# ASIC_1.net
KiCad netlist of a schematic drawn in Altium Designer
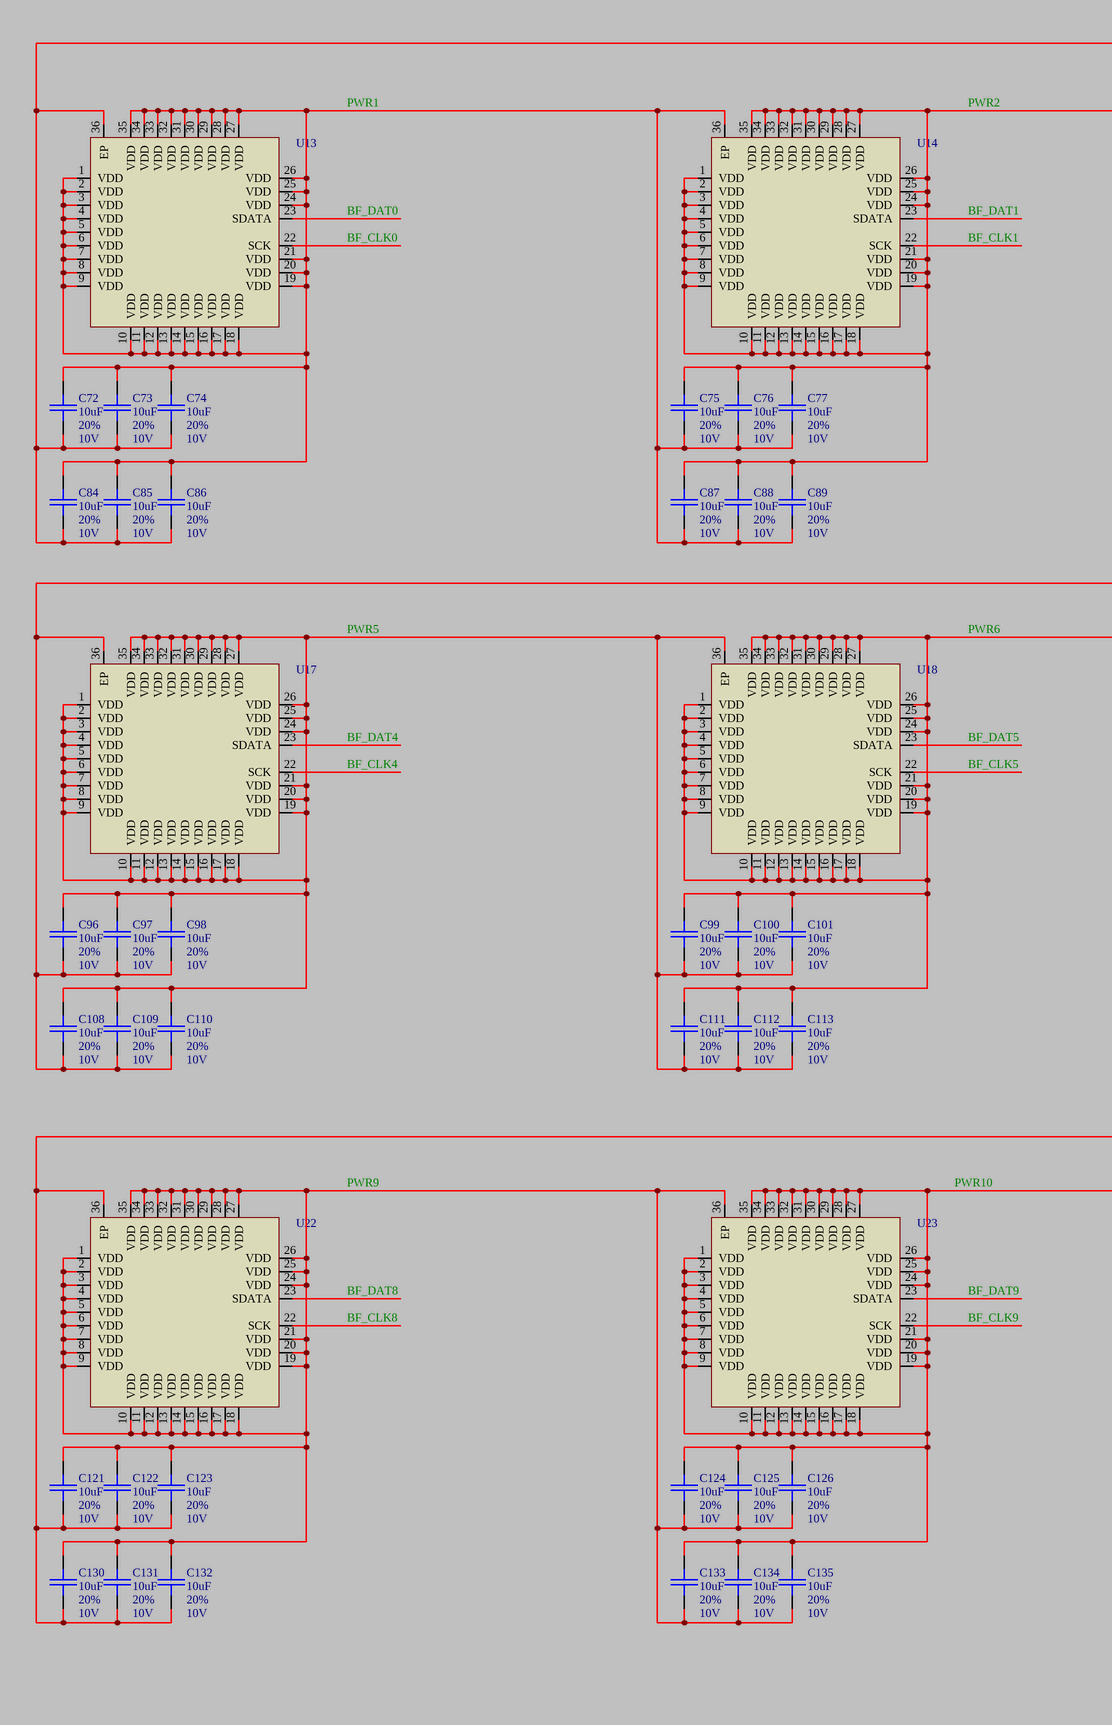
[diagram p0: ASIC_1.SchDoc, left]
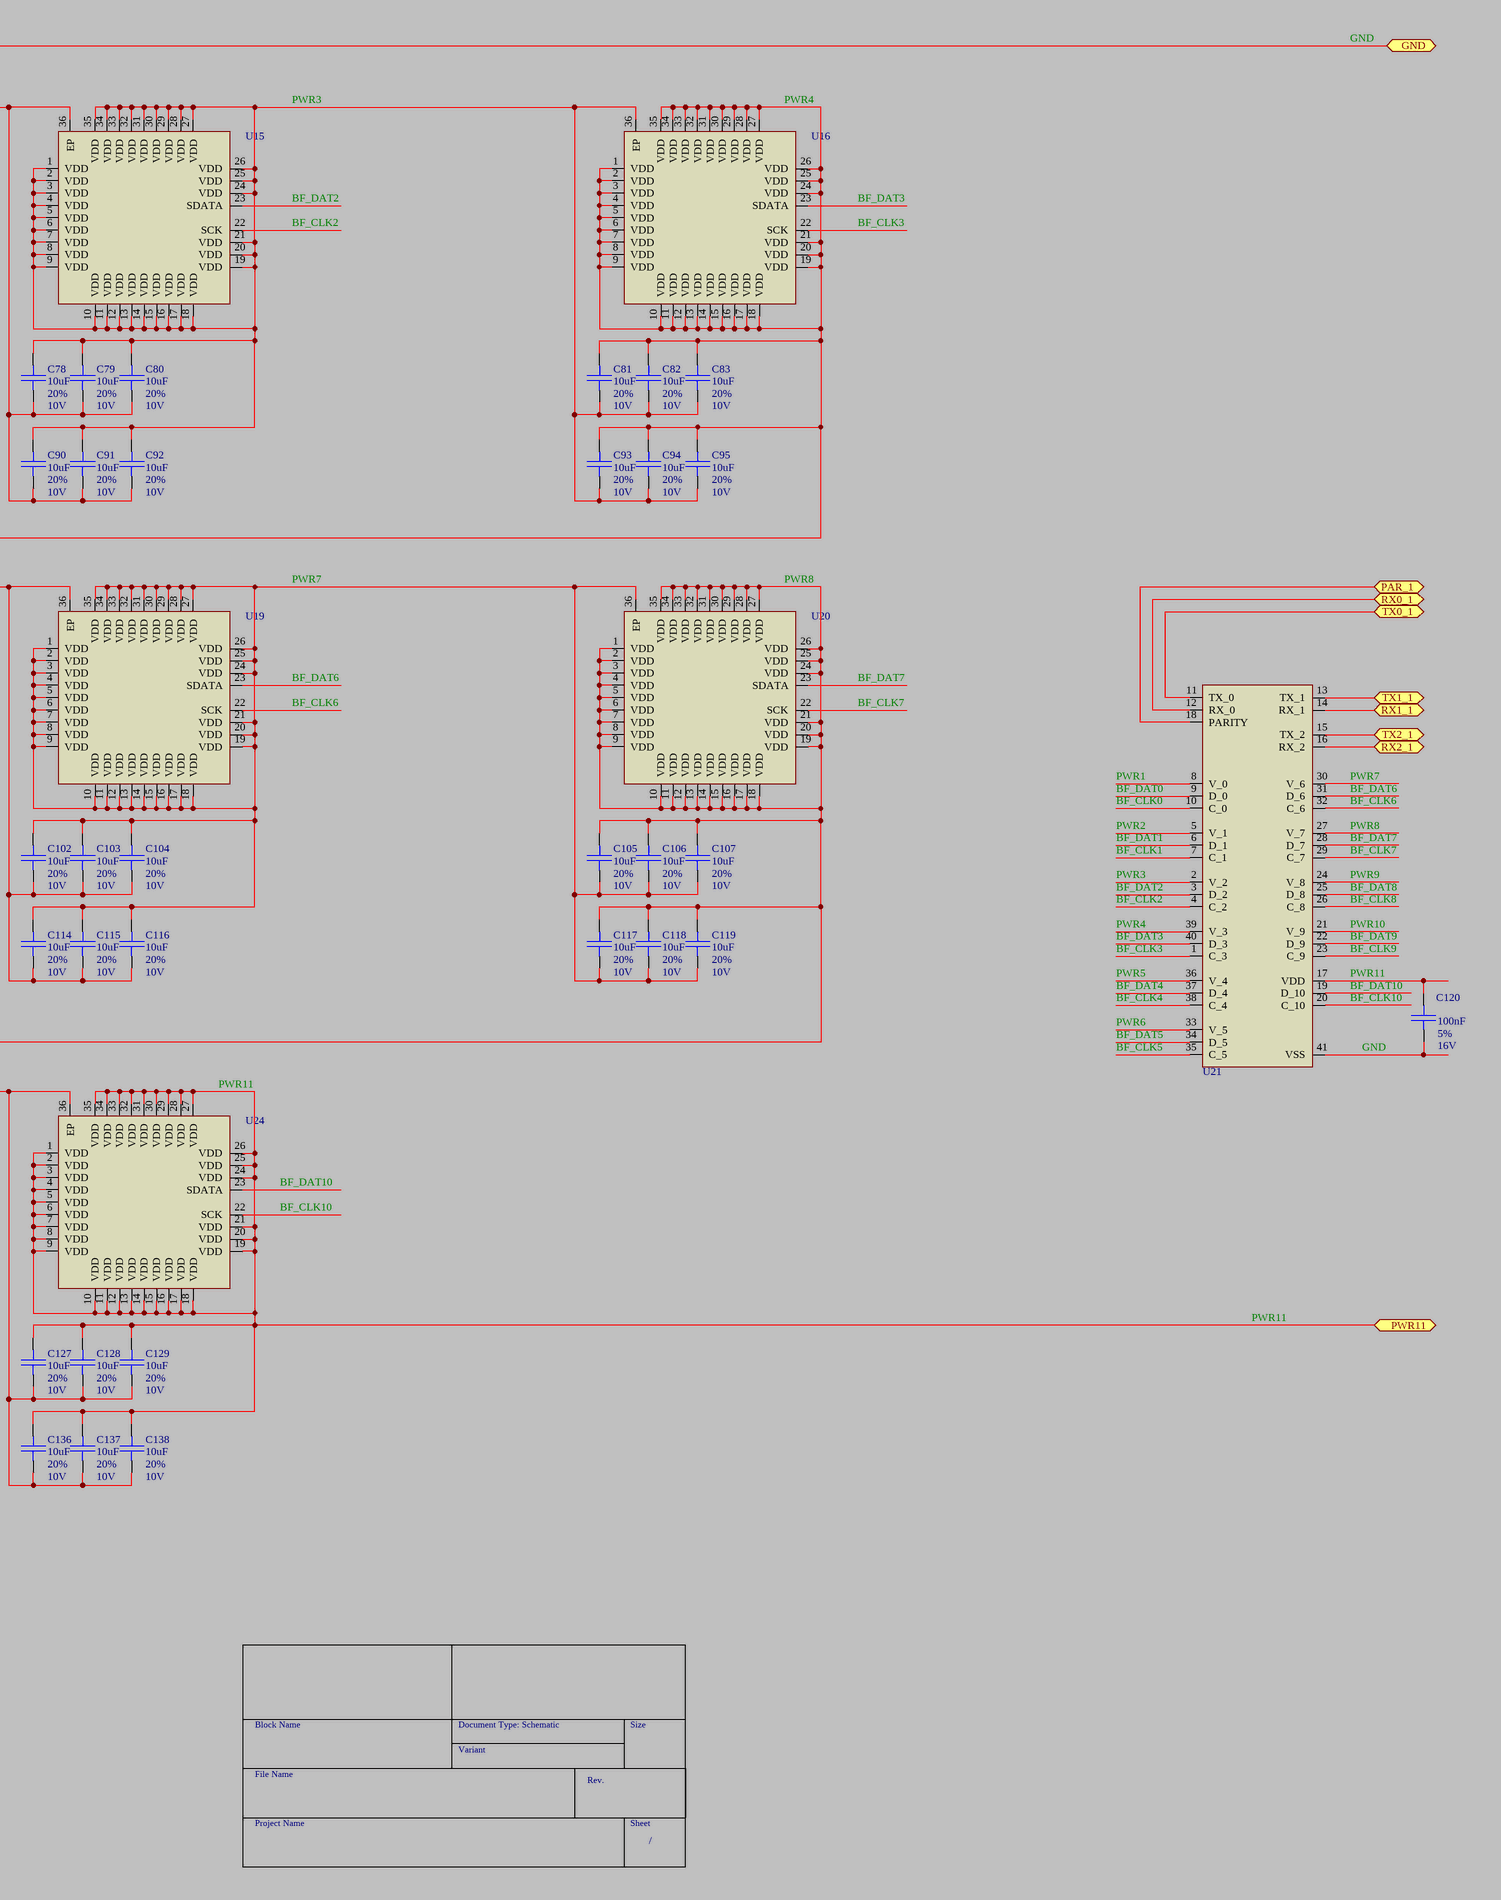
[diagram p1: ASIC_1.SchDoc, right]

(export (version "E")
  (design (tool "Eeschema 10.0.6"))
  (components
    (comp (ref "C72")
      (value "C")
      (footprint "SMD_0402_CAPC1005X70N")
      (fields
        (field (name "DB_PART_NUMBER") "CAP000047481")
        (field (name "DB_VALUE") "10uF")
        (field (name "DB_TOLERANCE") "20%")
        (field (name "DB_VOLTAGE") "10V")
        (field (name "DB_MANUFACTURER_PART") "SAMSUNG    CL05A106MP5NUNC")
        (field (name "DB_APPROVED_BY") "VSN")
      )
      (libsource (lib "Database_Libs1") (part "C"))
    )
    (comp (ref "C73")
      (value "C")
      (footprint "SMD_0402_CAPC1005X70N")
      (fields
        (field (name "DB_PART_NUMBER") "CAP000047481")
        (field (name "DB_VALUE") "10uF")
        (field (name "DB_TOLERANCE") "20%")
        (field (name "DB_VOLTAGE") "10V")
        (field (name "DB_MANUFACTURER_PART") "SAMSUNG    CL05A106MP5NUNC")
        (field (name "DB_APPROVED_BY") "VSN")
      )
      (libsource (lib "Database_Libs1") (part "C"))
    )
    (comp (ref "C74")
      (value "C")
      (footprint "SMD_0402_CAPC1005X70N")
      (fields
        (field (name "DB_PART_NUMBER") "CAP000047481")
        (field (name "DB_VALUE") "10uF")
        (field (name "DB_TOLERANCE") "20%")
        (field (name "DB_VOLTAGE") "10V")
        (field (name "DB_MANUFACTURER_PART") "SAMSUNG    CL05A106MP5NUNC")
        (field (name "DB_APPROVED_BY") "VSN")
      )
      (libsource (lib "Database_Libs1") (part "C"))
    )
    (comp (ref "C75")
      (value "C")
      (footprint "SMD_0402_CAPC1005X70N")
      (fields
        (field (name "DB_PART_NUMBER") "CAP000047481")
        (field (name "DB_VALUE") "10uF")
        (field (name "DB_TOLERANCE") "20%")
        (field (name "DB_VOLTAGE") "10V")
        (field (name "DB_MANUFACTURER_PART") "SAMSUNG    CL05A106MP5NUNC")
        (field (name "DB_APPROVED_BY") "VSN")
      )
      (libsource (lib "Database_Libs1") (part "C"))
    )
    (comp (ref "C76")
      (value "C")
      (footprint "SMD_0402_CAPC1005X70N")
      (fields
        (field (name "DB_PART_NUMBER") "CAP000047481")
        (field (name "DB_VALUE") "10uF")
        (field (name "DB_TOLERANCE") "20%")
        (field (name "DB_VOLTAGE") "10V")
        (field (name "DB_MANUFACTURER_PART") "SAMSUNG    CL05A106MP5NUNC")
        (field (name "DB_APPROVED_BY") "VSN")
      )
      (libsource (lib "Database_Libs1") (part "C"))
    )
    (comp (ref "C77")
      (value "C")
      (footprint "SMD_0402_CAPC1005X70N")
      (fields
        (field (name "DB_PART_NUMBER") "CAP000047481")
        (field (name "DB_VALUE") "10uF")
        (field (name "DB_TOLERANCE") "20%")
        (field (name "DB_VOLTAGE") "10V")
        (field (name "DB_MANUFACTURER_PART") "SAMSUNG    CL05A106MP5NUNC")
        (field (name "DB_APPROVED_BY") "VSN")
      )
      (libsource (lib "Database_Libs1") (part "C"))
    )
    (comp (ref "C78")
      (value "C")
      (footprint "SMD_0402_CAPC1005X70N")
      (fields
        (field (name "DB_PART_NUMBER") "CAP000047481")
        (field (name "DB_VALUE") "10uF")
        (field (name "DB_TOLERANCE") "20%")
        (field (name "DB_VOLTAGE") "10V")
        (field (name "DB_MANUFACTURER_PART") "SAMSUNG    CL05A106MP5NUNC")
        (field (name "DB_APPROVED_BY") "VSN")
      )
      (libsource (lib "Database_Libs1") (part "C"))
    )
    (comp (ref "C79")
      (value "C")
      (footprint "SMD_0402_CAPC1005X70N")
      (fields
        (field (name "DB_PART_NUMBER") "CAP000047481")
        (field (name "DB_VALUE") "10uF")
        (field (name "DB_TOLERANCE") "20%")
        (field (name "DB_VOLTAGE") "10V")
        (field (name "DB_MANUFACTURER_PART") "SAMSUNG    CL05A106MP5NUNC")
        (field (name "DB_APPROVED_BY") "VSN")
      )
      (libsource (lib "Database_Libs1") (part "C"))
    )
    (comp (ref "C80")
      (value "C")
      (footprint "SMD_0402_CAPC1005X70N")
      (fields
        (field (name "DB_PART_NUMBER") "CAP000047481")
        (field (name "DB_VALUE") "10uF")
        (field (name "DB_TOLERANCE") "20%")
        (field (name "DB_VOLTAGE") "10V")
        (field (name "DB_MANUFACTURER_PART") "SAMSUNG    CL05A106MP5NUNC")
        (field (name "DB_APPROVED_BY") "VSN")
      )
      (libsource (lib "Database_Libs1") (part "C"))
    )
    (comp (ref "C81")
      (value "C")
      (footprint "SMD_0402_CAPC1005X70N")
      (fields
        (field (name "DB_PART_NUMBER") "CAP000047481")
        (field (name "DB_VALUE") "10uF")
        (field (name "DB_TOLERANCE") "20%")
        (field (name "DB_VOLTAGE") "10V")
        (field (name "DB_MANUFACTURER_PART") "SAMSUNG    CL05A106MP5NUNC")
        (field (name "DB_APPROVED_BY") "VSN")
      )
      (libsource (lib "Database_Libs1") (part "C"))
    )
    (comp (ref "C82")
      (value "C")
      (footprint "SMD_0402_CAPC1005X70N")
      (fields
        (field (name "DB_PART_NUMBER") "CAP000047481")
        (field (name "DB_VALUE") "10uF")
        (field (name "DB_TOLERANCE") "20%")
        (field (name "DB_VOLTAGE") "10V")
        (field (name "DB_MANUFACTURER_PART") "SAMSUNG    CL05A106MP5NUNC")
        (field (name "DB_APPROVED_BY") "VSN")
      )
      (libsource (lib "Database_Libs1") (part "C"))
    )
    (comp (ref "C83")
      (value "C")
      (footprint "SMD_0402_CAPC1005X70N")
      (fields
        (field (name "DB_PART_NUMBER") "CAP000047481")
        (field (name "DB_VALUE") "10uF")
        (field (name "DB_TOLERANCE") "20%")
        (field (name "DB_VOLTAGE") "10V")
        (field (name "DB_MANUFACTURER_PART") "SAMSUNG    CL05A106MP5NUNC")
        (field (name "DB_APPROVED_BY") "VSN")
      )
      (libsource (lib "Database_Libs1") (part "C"))
    )
    (comp (ref "C84")
      (value "C")
      (footprint "SMD_0402_CAPC1005X70N")
      (fields
        (field (name "DB_PART_NUMBER") "CAP000047481")
        (field (name "DB_VALUE") "10uF")
        (field (name "DB_TOLERANCE") "20%")
        (field (name "DB_VOLTAGE") "10V")
        (field (name "DB_MANUFACTURER_PART") "SAMSUNG    CL05A106MP5NUNC")
        (field (name "DB_APPROVED_BY") "VSN")
      )
      (libsource (lib "Database_Libs1") (part "C"))
    )
    (comp (ref "C85")
      (value "C")
      (footprint "SMD_0402_CAPC1005X70N")
      (fields
        (field (name "DB_PART_NUMBER") "CAP000047481")
        (field (name "DB_VALUE") "10uF")
        (field (name "DB_TOLERANCE") "20%")
        (field (name "DB_VOLTAGE") "10V")
        (field (name "DB_MANUFACTURER_PART") "SAMSUNG    CL05A106MP5NUNC")
        (field (name "DB_APPROVED_BY") "VSN")
      )
      (libsource (lib "Database_Libs1") (part "C"))
    )
    (comp (ref "C86")
      (value "C")
      (footprint "SMD_0402_CAPC1005X70N")
      (fields
        (field (name "DB_PART_NUMBER") "CAP000047481")
        (field (name "DB_VALUE") "10uF")
        (field (name "DB_TOLERANCE") "20%")
        (field (name "DB_VOLTAGE") "10V")
        (field (name "DB_MANUFACTURER_PART") "SAMSUNG    CL05A106MP5NUNC")
        (field (name "DB_APPROVED_BY") "VSN")
      )
      (libsource (lib "Database_Libs1") (part "C"))
    )
    (comp (ref "C87")
      (value "C")
      (footprint "SMD_0402_CAPC1005X70N")
      (fields
        (field (name "DB_PART_NUMBER") "CAP000047481")
        (field (name "DB_VALUE") "10uF")
        (field (name "DB_TOLERANCE") "20%")
        (field (name "DB_VOLTAGE") "10V")
        (field (name "DB_MANUFACTURER_PART") "SAMSUNG    CL05A106MP5NUNC")
        (field (name "DB_APPROVED_BY") "VSN")
      )
      (libsource (lib "Database_Libs1") (part "C"))
    )
    (comp (ref "C88")
      (value "C")
      (footprint "SMD_0402_CAPC1005X70N")
      (fields
        (field (name "DB_PART_NUMBER") "CAP000047481")
        (field (name "DB_VALUE") "10uF")
        (field (name "DB_TOLERANCE") "20%")
        (field (name "DB_VOLTAGE") "10V")
        (field (name "DB_MANUFACTURER_PART") "SAMSUNG    CL05A106MP5NUNC")
        (field (name "DB_APPROVED_BY") "VSN")
      )
      (libsource (lib "Database_Libs1") (part "C"))
    )
    (comp (ref "C89")
      (value "C")
      (footprint "SMD_0402_CAPC1005X70N")
      (fields
        (field (name "DB_PART_NUMBER") "CAP000047481")
        (field (name "DB_VALUE") "10uF")
        (field (name "DB_TOLERANCE") "20%")
        (field (name "DB_VOLTAGE") "10V")
        (field (name "DB_MANUFACTURER_PART") "SAMSUNG    CL05A106MP5NUNC")
        (field (name "DB_APPROVED_BY") "VSN")
      )
      (libsource (lib "Database_Libs1") (part "C"))
    )
    (comp (ref "C90")
      (value "C")
      (footprint "SMD_0402_CAPC1005X70N")
      (fields
        (field (name "DB_PART_NUMBER") "CAP000047481")
        (field (name "DB_VALUE") "10uF")
        (field (name "DB_TOLERANCE") "20%")
        (field (name "DB_VOLTAGE") "10V")
        (field (name "DB_MANUFACTURER_PART") "SAMSUNG    CL05A106MP5NUNC")
        (field (name "DB_APPROVED_BY") "VSN")
      )
      (libsource (lib "Database_Libs1") (part "C"))
    )
    (comp (ref "C91")
      (value "C")
      (footprint "SMD_0402_CAPC1005X70N")
      (fields
        (field (name "DB_PART_NUMBER") "CAP000047481")
        (field (name "DB_VALUE") "10uF")
        (field (name "DB_TOLERANCE") "20%")
        (field (name "DB_VOLTAGE") "10V")
        (field (name "DB_MANUFACTURER_PART") "SAMSUNG    CL05A106MP5NUNC")
        (field (name "DB_APPROVED_BY") "VSN")
      )
      (libsource (lib "Database_Libs1") (part "C"))
    )
    (comp (ref "C92")
      (value "C")
      (footprint "SMD_0402_CAPC1005X70N")
      (fields
        (field (name "DB_PART_NUMBER") "CAP000047481")
        (field (name "DB_VALUE") "10uF")
        (field (name "DB_TOLERANCE") "20%")
        (field (name "DB_VOLTAGE") "10V")
        (field (name "DB_MANUFACTURER_PART") "SAMSUNG    CL05A106MP5NUNC")
        (field (name "DB_APPROVED_BY") "VSN")
      )
      (libsource (lib "Database_Libs1") (part "C"))
    )
    (comp (ref "C93")
      (value "C")
      (footprint "SMD_0402_CAPC1005X70N")
      (fields
        (field (name "DB_PART_NUMBER") "CAP000047481")
        (field (name "DB_VALUE") "10uF")
        (field (name "DB_TOLERANCE") "20%")
        (field (name "DB_VOLTAGE") "10V")
        (field (name "DB_MANUFACTURER_PART") "SAMSUNG    CL05A106MP5NUNC")
        (field (name "DB_APPROVED_BY") "VSN")
      )
      (libsource (lib "Database_Libs1") (part "C"))
    )
    (comp (ref "C94")
      (value "C")
      (footprint "SMD_0402_CAPC1005X70N")
      (fields
        (field (name "DB_PART_NUMBER") "CAP000047481")
        (field (name "DB_VALUE") "10uF")
        (field (name "DB_TOLERANCE") "20%")
        (field (name "DB_VOLTAGE") "10V")
        (field (name "DB_MANUFACTURER_PART") "SAMSUNG    CL05A106MP5NUNC")
        (field (name "DB_APPROVED_BY") "VSN")
      )
      (libsource (lib "Database_Libs1") (part "C"))
    )
    (comp (ref "C95")
      (value "C")
      (footprint "SMD_0402_CAPC1005X70N")
      (fields
        (field (name "DB_PART_NUMBER") "CAP000047481")
        (field (name "DB_VALUE") "10uF")
        (field (name "DB_TOLERANCE") "20%")
        (field (name "DB_VOLTAGE") "10V")
        (field (name "DB_MANUFACTURER_PART") "SAMSUNG    CL05A106MP5NUNC")
        (field (name "DB_APPROVED_BY") "VSN")
      )
      (libsource (lib "Database_Libs1") (part "C"))
    )
    (comp (ref "C96")
      (value "C")
      (footprint "SMD_0402_CAPC1005X70N")
      (fields
        (field (name "DB_PART_NUMBER") "CAP000047481")
        (field (name "DB_VALUE") "10uF")
        (field (name "DB_TOLERANCE") "20%")
        (field (name "DB_VOLTAGE") "10V")
        (field (name "DB_MANUFACTURER_PART") "SAMSUNG    CL05A106MP5NUNC")
        (field (name "DB_APPROVED_BY") "VSN")
      )
      (libsource (lib "Database_Libs1") (part "C"))
    )
    (comp (ref "C97")
      (value "C")
      (footprint "SMD_0402_CAPC1005X70N")
      (fields
        (field (name "DB_PART_NUMBER") "CAP000047481")
        (field (name "DB_VALUE") "10uF")
        (field (name "DB_TOLERANCE") "20%")
        (field (name "DB_VOLTAGE") "10V")
        (field (name "DB_MANUFACTURER_PART") "SAMSUNG    CL05A106MP5NUNC")
        (field (name "DB_APPROVED_BY") "VSN")
      )
      (libsource (lib "Database_Libs1") (part "C"))
    )
    (comp (ref "C98")
      (value "C")
      (footprint "SMD_0402_CAPC1005X70N")
      (fields
        (field (name "DB_PART_NUMBER") "CAP000047481")
        (field (name "DB_VALUE") "10uF")
        (field (name "DB_TOLERANCE") "20%")
        (field (name "DB_VOLTAGE") "10V")
        (field (name "DB_MANUFACTURER_PART") "SAMSUNG    CL05A106MP5NUNC")
        (field (name "DB_APPROVED_BY") "VSN")
      )
      (libsource (lib "Database_Libs1") (part "C"))
    )
    (comp (ref "C99")
      (value "C")
      (footprint "SMD_0402_CAPC1005X70N")
      (fields
        (field (name "DB_PART_NUMBER") "CAP000047481")
        (field (name "DB_VALUE") "10uF")
        (field (name "DB_TOLERANCE") "20%")
        (field (name "DB_VOLTAGE") "10V")
        (field (name "DB_MANUFACTURER_PART") "SAMSUNG    CL05A106MP5NUNC")
        (field (name "DB_APPROVED_BY") "VSN")
      )
      (libsource (lib "Database_Libs1") (part "C"))
    )
    (comp (ref "C100")
      (value "C")
      (footprint "SMD_0402_CAPC1005X70N")
      (fields
        (field (name "DB_PART_NUMBER") "CAP000047481")
        (field (name "DB_VALUE") "10uF")
        (field (name "DB_TOLERANCE") "20%")
        (field (name "DB_VOLTAGE") "10V")
        (field (name "DB_MANUFACTURER_PART") "SAMSUNG    CL05A106MP5NUNC")
        (field (name "DB_APPROVED_BY") "VSN")
      )
      (libsource (lib "Database_Libs1") (part "C"))
    )
    (comp (ref "C101")
      (value "C")
      (footprint "SMD_0402_CAPC1005X70N")
      (fields
        (field (name "DB_PART_NUMBER") "CAP000047481")
        (field (name "DB_VALUE") "10uF")
        (field (name "DB_TOLERANCE") "20%")
        (field (name "DB_VOLTAGE") "10V")
        (field (name "DB_MANUFACTURER_PART") "SAMSUNG    CL05A106MP5NUNC")
        (field (name "DB_APPROVED_BY") "VSN")
      )
      (libsource (lib "Database_Libs1") (part "C"))
    )
    (comp (ref "C102")
      (value "C")
      (footprint "SMD_0402_CAPC1005X70N")
      (fields
        (field (name "DB_PART_NUMBER") "CAP000047481")
        (field (name "DB_VALUE") "10uF")
        (field (name "DB_TOLERANCE") "20%")
        (field (name "DB_VOLTAGE") "10V")
        (field (name "DB_MANUFACTURER_PART") "SAMSUNG    CL05A106MP5NUNC")
        (field (name "DB_APPROVED_BY") "VSN")
      )
      (libsource (lib "Database_Libs1") (part "C"))
    )
    (comp (ref "C103")
      (value "C")
      (footprint "SMD_0402_CAPC1005X70N")
      (fields
        (field (name "DB_PART_NUMBER") "CAP000047481")
        (field (name "DB_VALUE") "10uF")
        (field (name "DB_TOLERANCE") "20%")
        (field (name "DB_VOLTAGE") "10V")
        (field (name "DB_MANUFACTURER_PART") "SAMSUNG    CL05A106MP5NUNC")
        (field (name "DB_APPROVED_BY") "VSN")
      )
      (libsource (lib "Database_Libs1") (part "C"))
    )
    (comp (ref "C104")
      (value "C")
      (footprint "SMD_0402_CAPC1005X70N")
      (fields
        (field (name "DB_PART_NUMBER") "CAP000047481")
        (field (name "DB_VALUE") "10uF")
        (field (name "DB_TOLERANCE") "20%")
        (field (name "DB_VOLTAGE") "10V")
        (field (name "DB_MANUFACTURER_PART") "SAMSUNG    CL05A106MP5NUNC")
        (field (name "DB_APPROVED_BY") "VSN")
      )
      (libsource (lib "Database_Libs1") (part "C"))
    )
    (comp (ref "C105")
      (value "C")
      (footprint "SMD_0402_CAPC1005X70N")
      (fields
        (field (name "DB_PART_NUMBER") "CAP000047481")
        (field (name "DB_VALUE") "10uF")
        (field (name "DB_TOLERANCE") "20%")
        (field (name "DB_VOLTAGE") "10V")
        (field (name "DB_MANUFACTURER_PART") "SAMSUNG    CL05A106MP5NUNC")
        (field (name "DB_APPROVED_BY") "VSN")
      )
      (libsource (lib "Database_Libs1") (part "C"))
    )
    (comp (ref "C106")
      (value "C")
      (footprint "SMD_0402_CAPC1005X70N")
      (fields
        (field (name "DB_PART_NUMBER") "CAP000047481")
        (field (name "DB_VALUE") "10uF")
        (field (name "DB_TOLERANCE") "20%")
        (field (name "DB_VOLTAGE") "10V")
        (field (name "DB_MANUFACTURER_PART") "SAMSUNG    CL05A106MP5NUNC")
        (field (name "DB_APPROVED_BY") "VSN")
      )
      (libsource (lib "Database_Libs1") (part "C"))
    )
    (comp (ref "C107")
      (value "C")
      (footprint "SMD_0402_CAPC1005X70N")
      (fields
        (field (name "DB_PART_NUMBER") "CAP000047481")
        (field (name "DB_VALUE") "10uF")
        (field (name "DB_TOLERANCE") "20%")
        (field (name "DB_VOLTAGE") "10V")
        (field (name "DB_MANUFACTURER_PART") "SAMSUNG    CL05A106MP5NUNC")
        (field (name "DB_APPROVED_BY") "VSN")
      )
      (libsource (lib "Database_Libs1") (part "C"))
    )
    (comp (ref "C108")
      (value "C")
      (footprint "SMD_0402_CAPC1005X70N")
      (fields
        (field (name "DB_PART_NUMBER") "CAP000047481")
        (field (name "DB_VALUE") "10uF")
        (field (name "DB_TOLERANCE") "20%")
        (field (name "DB_VOLTAGE") "10V")
        (field (name "DB_MANUFACTURER_PART") "SAMSUNG    CL05A106MP5NUNC")
        (field (name "DB_APPROVED_BY") "VSN")
      )
      (libsource (lib "Database_Libs1") (part "C"))
    )
    (comp (ref "C109")
      (value "C")
      (footprint "SMD_0402_CAPC1005X70N")
      (fields
        (field (name "DB_PART_NUMBER") "CAP000047481")
        (field (name "DB_VALUE") "10uF")
        (field (name "DB_TOLERANCE") "20%")
        (field (name "DB_VOLTAGE") "10V")
        (field (name "DB_MANUFACTURER_PART") "SAMSUNG    CL05A106MP5NUNC")
        (field (name "DB_APPROVED_BY") "VSN")
      )
      (libsource (lib "Database_Libs1") (part "C"))
    )
    (comp (ref "C110")
      (value "C")
      (footprint "SMD_0402_CAPC1005X70N")
      (fields
        (field (name "DB_PART_NUMBER") "CAP000047481")
        (field (name "DB_VALUE") "10uF")
        (field (name "DB_TOLERANCE") "20%")
        (field (name "DB_VOLTAGE") "10V")
        (field (name "DB_MANUFACTURER_PART") "SAMSUNG    CL05A106MP5NUNC")
        (field (name "DB_APPROVED_BY") "VSN")
      )
      (libsource (lib "Database_Libs1") (part "C"))
    )
    (comp (ref "C111")
      (value "C")
      (footprint "SMD_0402_CAPC1005X70N")
      (fields
        (field (name "DB_PART_NUMBER") "CAP000047481")
        (field (name "DB_VALUE") "10uF")
        (field (name "DB_TOLERANCE") "20%")
        (field (name "DB_VOLTAGE") "10V")
        (field (name "DB_MANUFACTURER_PART") "SAMSUNG    CL05A106MP5NUNC")
        (field (name "DB_APPROVED_BY") "VSN")
      )
      (libsource (lib "Database_Libs1") (part "C"))
    )
    (comp (ref "C112")
      (value "C")
      (footprint "SMD_0402_CAPC1005X70N")
      (fields
        (field (name "DB_PART_NUMBER") "CAP000047481")
        (field (name "DB_VALUE") "10uF")
        (field (name "DB_TOLERANCE") "20%")
        (field (name "DB_VOLTAGE") "10V")
        (field (name "DB_MANUFACTURER_PART") "SAMSUNG    CL05A106MP5NUNC")
        (field (name "DB_APPROVED_BY") "VSN")
      )
      (libsource (lib "Database_Libs1") (part "C"))
    )
    (comp (ref "C113")
      (value "C")
      (footprint "SMD_0402_CAPC1005X70N")
      (fields
        (field (name "DB_PART_NUMBER") "CAP000047481")
        (field (name "DB_VALUE") "10uF")
        (field (name "DB_TOLERANCE") "20%")
        (field (name "DB_VOLTAGE") "10V")
        (field (name "DB_MANUFACTURER_PART") "SAMSUNG    CL05A106MP5NUNC")
        (field (name "DB_APPROVED_BY") "VSN")
      )
      (libsource (lib "Database_Libs1") (part "C"))
    )
    (comp (ref "C114")
      (value "C")
      (footprint "SMD_0402_CAPC1005X70N")
      (fields
        (field (name "DB_PART_NUMBER") "CAP000047481")
        (field (name "DB_VALUE") "10uF")
        (field (name "DB_TOLERANCE") "20%")
        (field (name "DB_VOLTAGE") "10V")
        (field (name "DB_MANUFACTURER_PART") "SAMSUNG    CL05A106MP5NUNC")
        (field (name "DB_APPROVED_BY") "VSN")
      )
      (libsource (lib "Database_Libs1") (part "C"))
    )
    (comp (ref "C115")
      (value "C")
      (footprint "SMD_0402_CAPC1005X70N")
      (fields
        (field (name "DB_PART_NUMBER") "CAP000047481")
        (field (name "DB_VALUE") "10uF")
        (field (name "DB_TOLERANCE") "20%")
        (field (name "DB_VOLTAGE") "10V")
        (field (name "DB_MANUFACTURER_PART") "SAMSUNG    CL05A106MP5NUNC")
        (field (name "DB_APPROVED_BY") "VSN")
      )
      (libsource (lib "Database_Libs1") (part "C"))
    )
    (comp (ref "C116")
      (value "C")
      (footprint "SMD_0402_CAPC1005X70N")
      (fields
        (field (name "DB_PART_NUMBER") "CAP000047481")
        (field (name "DB_VALUE") "10uF")
        (field (name "DB_TOLERANCE") "20%")
        (field (name "DB_VOLTAGE") "10V")
        (field (name "DB_MANUFACTURER_PART") "SAMSUNG    CL05A106MP5NUNC")
        (field (name "DB_APPROVED_BY") "VSN")
      )
      (libsource (lib "Database_Libs1") (part "C"))
    )
    (comp (ref "C117")
      (value "C")
      (footprint "SMD_0402_CAPC1005X70N")
      (fields
        (field (name "DB_PART_NUMBER") "CAP000047481")
        (field (name "DB_VALUE") "10uF")
        (field (name "DB_TOLERANCE") "20%")
        (field (name "DB_VOLTAGE") "10V")
        (field (name "DB_MANUFACTURER_PART") "SAMSUNG    CL05A106MP5NUNC")
        (field (name "DB_APPROVED_BY") "VSN")
      )
      (libsource (lib "Database_Libs1") (part "C"))
    )
    (comp (ref "C118")
      (value "C")
      (footprint "SMD_0402_CAPC1005X70N")
      (fields
        (field (name "DB_PART_NUMBER") "CAP000047481")
        (field (name "DB_VALUE") "10uF")
        (field (name "DB_TOLERANCE") "20%")
        (field (name "DB_VOLTAGE") "10V")
        (field (name "DB_MANUFACTURER_PART") "SAMSUNG    CL05A106MP5NUNC")
        (field (name "DB_APPROVED_BY") "VSN")
      )
      (libsource (lib "Database_Libs1") (part "C"))
    )
    (comp (ref "C119")
      (value "C")
      (footprint "SMD_0402_CAPC1005X70N")
      (fields
        (field (name "DB_PART_NUMBER") "CAP000047481")
        (field (name "DB_VALUE") "10uF")
        (field (name "DB_TOLERANCE") "20%")
        (field (name "DB_VOLTAGE") "10V")
        (field (name "DB_MANUFACTURER_PART") "SAMSUNG    CL05A106MP5NUNC")
        (field (name "DB_APPROVED_BY") "VSN")
      )
      (libsource (lib "Database_Libs1") (part "C"))
    )
    (comp (ref "C120")
      (value "C")
      (footprint "SMD_0603_CAPC1608X95N")
      (fields
        (field (name "DB_PART_NUMBER") "CAP000027134")
        (field (name "DB_VALUE") "100nF")
        (field (name "DB_TOLERANCE") "5%")
        (field (name "DB_VOLTAGE") "16V")
        (field (name "DB_MANUFACTURER_PART") "KEMET    C0603C104J4RAC")
      )
      (libsource (lib "Database_Libs1") (part "C"))
    )
    (comp (ref "C121")
      (value "C")
      (footprint "SMD_0402_CAPC1005X70N")
      (fields
        (field (name "DB_PART_NUMBER") "CAP000047481")
        (field (name "DB_VALUE") "10uF")
        (field (name "DB_TOLERANCE") "20%")
        (field (name "DB_VOLTAGE") "10V")
        (field (name "DB_MANUFACTURER_PART") "SAMSUNG    CL05A106MP5NUNC")
        (field (name "DB_APPROVED_BY") "VSN")
      )
      (libsource (lib "Database_Libs1") (part "C"))
    )
    (comp (ref "C122")
      (value "C")
      (footprint "SMD_0402_CAPC1005X70N")
      (fields
        (field (name "DB_PART_NUMBER") "CAP000047481")
        (field (name "DB_VALUE") "10uF")
        (field (name "DB_TOLERANCE") "20%")
        (field (name "DB_VOLTAGE") "10V")
        (field (name "DB_MANUFACTURER_PART") "SAMSUNG    CL05A106MP5NUNC")
        (field (name "DB_APPROVED_BY") "VSN")
      )
      (libsource (lib "Database_Libs1") (part "C"))
    )
    (comp (ref "C123")
      (value "C")
      (footprint "SMD_0402_CAPC1005X70N")
      (fields
        (field (name "DB_PART_NUMBER") "CAP000047481")
        (field (name "DB_VALUE") "10uF")
        (field (name "DB_TOLERANCE") "20%")
        (field (name "DB_VOLTAGE") "10V")
        (field (name "DB_MANUFACTURER_PART") "SAMSUNG    CL05A106MP5NUNC")
        (field (name "DB_APPROVED_BY") "VSN")
      )
      (libsource (lib "Database_Libs1") (part "C"))
    )
    (comp (ref "C124")
      (value "C")
      (footprint "SMD_0402_CAPC1005X70N")
      (fields
        (field (name "DB_PART_NUMBER") "CAP000047481")
        (field (name "DB_VALUE") "10uF")
        (field (name "DB_TOLERANCE") "20%")
        (field (name "DB_VOLTAGE") "10V")
        (field (name "DB_MANUFACTURER_PART") "SAMSUNG    CL05A106MP5NUNC")
        (field (name "DB_APPROVED_BY") "VSN")
      )
      (libsource (lib "Database_Libs1") (part "C"))
    )
    (comp (ref "C125")
      (value "C")
      (footprint "SMD_0402_CAPC1005X70N")
      (fields
        (field (name "DB_PART_NUMBER") "CAP000047481")
        (field (name "DB_VALUE") "10uF")
        (field (name "DB_TOLERANCE") "20%")
        (field (name "DB_VOLTAGE") "10V")
        (field (name "DB_MANUFACTURER_PART") "SAMSUNG    CL05A106MP5NUNC")
        (field (name "DB_APPROVED_BY") "VSN")
      )
      (libsource (lib "Database_Libs1") (part "C"))
    )
    (comp (ref "C126")
      (value "C")
      (footprint "SMD_0402_CAPC1005X70N")
      (fields
        (field (name "DB_PART_NUMBER") "CAP000047481")
        (field (name "DB_VALUE") "10uF")
        (field (name "DB_TOLERANCE") "20%")
        (field (name "DB_VOLTAGE") "10V")
        (field (name "DB_MANUFACTURER_PART") "SAMSUNG    CL05A106MP5NUNC")
        (field (name "DB_APPROVED_BY") "VSN")
      )
      (libsource (lib "Database_Libs1") (part "C"))
    )
    (comp (ref "C127")
      (value "C")
      (footprint "SMD_0402_CAPC1005X70N")
      (fields
        (field (name "DB_PART_NUMBER") "CAP000047481")
        (field (name "DB_VALUE") "10uF")
        (field (name "DB_TOLERANCE") "20%")
        (field (name "DB_VOLTAGE") "10V")
        (field (name "DB_MANUFACTURER_PART") "SAMSUNG    CL05A106MP5NUNC")
        (field (name "DB_APPROVED_BY") "VSN")
      )
      (libsource (lib "Database_Libs1") (part "C"))
    )
    (comp (ref "C128")
      (value "C")
      (footprint "SMD_0402_CAPC1005X70N")
      (fields
        (field (name "DB_PART_NUMBER") "CAP000047481")
        (field (name "DB_VALUE") "10uF")
        (field (name "DB_TOLERANCE") "20%")
        (field (name "DB_VOLTAGE") "10V")
        (field (name "DB_MANUFACTURER_PART") "SAMSUNG    CL05A106MP5NUNC")
        (field (name "DB_APPROVED_BY") "VSN")
      )
      (libsource (lib "Database_Libs1") (part "C"))
    )
    (comp (ref "C129")
      (value "C")
      (footprint "SMD_0402_CAPC1005X70N")
      (fields
        (field (name "DB_PART_NUMBER") "CAP000047481")
        (field (name "DB_VALUE") "10uF")
        (field (name "DB_TOLERANCE") "20%")
        (field (name "DB_VOLTAGE") "10V")
        (field (name "DB_MANUFACTURER_PART") "SAMSUNG    CL05A106MP5NUNC")
        (field (name "DB_APPROVED_BY") "VSN")
      )
      (libsource (lib "Database_Libs1") (part "C"))
    )
    (comp (ref "C130")
      (value "C")
      (footprint "SMD_0402_CAPC1005X70N")
      (fields
        (field (name "DB_PART_NUMBER") "CAP000047481")
        (field (name "DB_VALUE") "10uF")
        (field (name "DB_TOLERANCE") "20%")
        (field (name "DB_VOLTAGE") "10V")
        (field (name "DB_MANUFACTURER_PART") "SAMSUNG    CL05A106MP5NUNC")
        (field (name "DB_APPROVED_BY") "VSN")
      )
      (libsource (lib "Database_Libs1") (part "C"))
    )
    (comp (ref "C131")
      (value "C")
      (footprint "SMD_0402_CAPC1005X70N")
      (fields
        (field (name "DB_PART_NUMBER") "CAP000047481")
        (field (name "DB_VALUE") "10uF")
        (field (name "DB_TOLERANCE") "20%")
        (field (name "DB_VOLTAGE") "10V")
        (field (name "DB_MANUFACTURER_PART") "SAMSUNG    CL05A106MP5NUNC")
        (field (name "DB_APPROVED_BY") "VSN")
      )
      (libsource (lib "Database_Libs1") (part "C"))
    )
    (comp (ref "C132")
      (value "C")
      (footprint "SMD_0402_CAPC1005X70N")
      (fields
        (field (name "DB_PART_NUMBER") "CAP000047481")
        (field (name "DB_VALUE") "10uF")
        (field (name "DB_TOLERANCE") "20%")
        (field (name "DB_VOLTAGE") "10V")
        (field (name "DB_MANUFACTURER_PART") "SAMSUNG    CL05A106MP5NUNC")
        (field (name "DB_APPROVED_BY") "VSN")
      )
      (libsource (lib "Database_Libs1") (part "C"))
    )
    (comp (ref "C133")
      (value "C")
      (footprint "SMD_0402_CAPC1005X70N")
      (fields
        (field (name "DB_PART_NUMBER") "CAP000047481")
        (field (name "DB_VALUE") "10uF")
        (field (name "DB_TOLERANCE") "20%")
        (field (name "DB_VOLTAGE") "10V")
        (field (name "DB_MANUFACTURER_PART") "SAMSUNG    CL05A106MP5NUNC")
        (field (name "DB_APPROVED_BY") "VSN")
      )
      (libsource (lib "Database_Libs1") (part "C"))
    )
    (comp (ref "C134")
      (value "C")
      (footprint "SMD_0402_CAPC1005X70N")
      (fields
        (field (name "DB_PART_NUMBER") "CAP000047481")
        (field (name "DB_VALUE") "10uF")
        (field (name "DB_TOLERANCE") "20%")
        (field (name "DB_VOLTAGE") "10V")
        (field (name "DB_MANUFACTURER_PART") "SAMSUNG    CL05A106MP5NUNC")
        (field (name "DB_APPROVED_BY") "VSN")
      )
      (libsource (lib "Database_Libs1") (part "C"))
    )
    (comp (ref "C135")
      (value "C")
      (footprint "SMD_0402_CAPC1005X70N")
      (fields
        (field (name "DB_PART_NUMBER") "CAP000047481")
        (field (name "DB_VALUE") "10uF")
        (field (name "DB_TOLERANCE") "20%")
        (field (name "DB_VOLTAGE") "10V")
        (field (name "DB_MANUFACTURER_PART") "SAMSUNG    CL05A106MP5NUNC")
        (field (name "DB_APPROVED_BY") "VSN")
      )
      (libsource (lib "Database_Libs1") (part "C"))
    )
    (comp (ref "C136")
      (value "C")
      (footprint "SMD_0402_CAPC1005X70N")
      (fields
        (field (name "DB_PART_NUMBER") "CAP000047481")
        (field (name "DB_VALUE") "10uF")
        (field (name "DB_TOLERANCE") "20%")
        (field (name "DB_VOLTAGE") "10V")
        (field (name "DB_MANUFACTURER_PART") "SAMSUNG    CL05A106MP5NUNC")
        (field (name "DB_APPROVED_BY") "VSN")
      )
      (libsource (lib "Database_Libs1") (part "C"))
    )
    (comp (ref "C137")
      (value "C")
      (footprint "SMD_0402_CAPC1005X70N")
      (fields
        (field (name "DB_PART_NUMBER") "CAP000047481")
        (field (name "DB_VALUE") "10uF")
        (field (name "DB_TOLERANCE") "20%")
        (field (name "DB_VOLTAGE") "10V")
        (field (name "DB_MANUFACTURER_PART") "SAMSUNG    CL05A106MP5NUNC")
        (field (name "DB_APPROVED_BY") "VSN")
      )
      (libsource (lib "Database_Libs1") (part "C"))
    )
    (comp (ref "C138")
      (value "C")
      (footprint "SMD_0402_CAPC1005X70N")
      (fields
        (field (name "DB_PART_NUMBER") "CAP000047481")
        (field (name "DB_VALUE") "10uF")
        (field (name "DB_TOLERANCE") "20%")
        (field (name "DB_VOLTAGE") "10V")
        (field (name "DB_MANUFACTURER_PART") "SAMSUNG    CL05A106MP5NUNC")
        (field (name "DB_APPROVED_BY") "VSN")
      )
      (libsource (lib "Database_Libs1") (part "C"))
    )
    (comp (ref "U13")
      (value "IC_BITFURY16")
      (footprint "SMD_QFN50P600X600X175-36AN")
      (description "BitFury 2016 16 nm")
      (libsource (lib "BitCoin") (part "IC_BITFURY16"))
    )
    (comp (ref "U14")
      (value "IC_BITFURY16")
      (footprint "SMD_QFN50P600X600X175-36AN")
      (description "BitFury 2016 16 nm")
      (libsource (lib "BitCoin") (part "IC_BITFURY16"))
    )
    (comp (ref "U15")
      (value "IC_BITFURY16")
      (footprint "SMD_QFN50P600X600X175-36AN")
      (description "BitFury 2016 16 nm")
      (libsource (lib "BitCoin") (part "IC_BITFURY16"))
    )
    (comp (ref "U16")
      (value "IC_BITFURY16")
      (footprint "SMD_QFN50P600X600X175-36AN")
      (description "BitFury 2016 16 nm")
      (libsource (lib "BitCoin") (part "IC_BITFURY16"))
    )
    (comp (ref "U17")
      (value "IC_BITFURY16")
      (footprint "SMD_QFN50P600X600X175-36AN")
      (description "BitFury 2016 16 nm")
      (libsource (lib "BitCoin") (part "IC_BITFURY16"))
    )
    (comp (ref "U18")
      (value "IC_BITFURY16")
      (footprint "SMD_QFN50P600X600X175-36AN")
      (description "BitFury 2016 16 nm")
      (libsource (lib "BitCoin") (part "IC_BITFURY16"))
    )
    (comp (ref "U19")
      (value "IC_BITFURY16")
      (footprint "SMD_QFN50P600X600X175-36AN")
      (description "BitFury 2016 16 nm")
      (libsource (lib "BitCoin") (part "IC_BITFURY16"))
    )
    (comp (ref "U20")
      (value "IC_BITFURY16")
      (footprint "SMD_QFN50P600X600X175-36AN")
      (description "BitFury 2016 16 nm")
      (libsource (lib "BitCoin") (part "IC_BITFURY16"))
    )
    (comp (ref "U21")
      (value "IC_BTC250")
      (footprint "SMD_QFN40P500X500X80-41N")
      (fields (field (name "DB_MANUFACTURER_PART") "BTC250 QFN40 EP"))
      (libsource (lib "BitCoin") (part "IC_BTC250"))
    )
    (comp (ref "U22")
      (value "IC_BITFURY16")
      (footprint "SMD_QFN50P600X600X175-36AN")
      (description "BitFury 2016 16 nm")
      (libsource (lib "BitCoin") (part "IC_BITFURY16"))
    )
    (comp (ref "U23")
      (value "IC_BITFURY16")
      (footprint "SMD_QFN50P600X600X175-36AN")
      (description "BitFury 2016 16 nm")
      (libsource (lib "BitCoin") (part "IC_BITFURY16"))
    )
    (comp (ref "U24")
      (value "IC_BITFURY16")
      (footprint "SMD_QFN50P600X600X175-36AN")
      (description "BitFury 2016 16 nm")
      (libsource (lib "BitCoin") (part "IC_BITFURY16"))
    )
  )
  (nets
    (net (code "1") (name "/BF_CLK0") (class "Default")
      (node (ref "U13") (pin "22") (pinfunction "SCK_22") (pintype "passive"))
      (node (ref "U21") (pin "10") (pinfunction "C_0_10") (pintype "passive"))
    )
    (net (code "2") (name "/BF_CLK1") (class "Default")
      (node (ref "U14") (pin "22") (pinfunction "SCK_22") (pintype "passive"))
      (node (ref "U21") (pin "7") (pinfunction "C_1_7") (pintype "passive"))
    )
    (net (code "3") (name "/BF_CLK2") (class "Default")
      (node (ref "U15") (pin "22") (pinfunction "SCK_22") (pintype "passive"))
      (node (ref "U21") (pin "4") (pinfunction "C_2_4") (pintype "passive"))
    )
    (net (code "4") (name "/BF_CLK3") (class "Default")
      (node (ref "U16") (pin "22") (pinfunction "SCK_22") (pintype "passive"))
      (node (ref "U21") (pin "1") (pinfunction "C_3_1") (pintype "passive"))
    )
    (net (code "5") (name "/BF_CLK4") (class "Default")
      (node (ref "U17") (pin "22") (pinfunction "SCK_22") (pintype "passive"))
      (node (ref "U21") (pin "38") (pinfunction "C_4_38") (pintype "passive"))
    )
    (net (code "6") (name "/BF_CLK5") (class "Default")
      (node (ref "U18") (pin "22") (pinfunction "SCK_22") (pintype "passive"))
      (node (ref "U21") (pin "35") (pinfunction "C_5_35") (pintype "passive"))
    )
    (net (code "7") (name "/BF_CLK6") (class "Default")
      (node (ref "U19") (pin "22") (pinfunction "SCK_22") (pintype "passive"))
      (node (ref "U21") (pin "32") (pinfunction "C_6_32") (pintype "passive"))
    )
    (net (code "8") (name "/BF_CLK7") (class "Default")
      (node (ref "U20") (pin "22") (pinfunction "SCK_22") (pintype "passive"))
      (node (ref "U21") (pin "29") (pinfunction "C_7_29") (pintype "passive"))
    )
    (net (code "9") (name "/BF_CLK8") (class "Default")
      (node (ref "U21") (pin "26") (pinfunction "C_8_26") (pintype "passive"))
      (node (ref "U22") (pin "22") (pinfunction "SCK_22") (pintype "passive"))
    )
    (net (code "10") (name "/BF_CLK9") (class "Default")
      (node (ref "U21") (pin "23") (pinfunction "C_9_23") (pintype "passive"))
      (node (ref "U23") (pin "22") (pinfunction "SCK_22") (pintype "passive"))
    )
    (net (code "11") (name "/BF_CLK10") (class "Default")
      (node (ref "U21") (pin "20") (pinfunction "C_10_20") (pintype "passive"))
      (node (ref "U24") (pin "22") (pinfunction "SCK_22") (pintype "passive"))
    )
    (net (code "12") (name "/BF_DAT0") (class "Default")
      (node (ref "U13") (pin "23") (pinfunction "SDATA_23") (pintype "passive"))
      (node (ref "U21") (pin "9") (pinfunction "D_0_9") (pintype "passive"))
    )
    (net (code "13") (name "/BF_DAT1") (class "Default")
      (node (ref "U14") (pin "23") (pinfunction "SDATA_23") (pintype "passive"))
      (node (ref "U21") (pin "6") (pinfunction "D_1_6") (pintype "passive"))
    )
    (net (code "14") (name "/BF_DAT2") (class "Default")
      (node (ref "U15") (pin "23") (pinfunction "SDATA_23") (pintype "passive"))
      (node (ref "U21") (pin "3") (pinfunction "D_2_3") (pintype "passive"))
    )
    (net (code "15") (name "/BF_DAT3") (class "Default")
      (node (ref "U16") (pin "23") (pinfunction "SDATA_23") (pintype "passive"))
      (node (ref "U21") (pin "40") (pinfunction "D_3_40") (pintype "passive"))
    )
    (net (code "16") (name "/BF_DAT4") (class "Default")
      (node (ref "U17") (pin "23") (pinfunction "SDATA_23") (pintype "passive"))
      (node (ref "U21") (pin "37") (pinfunction "D_4_37") (pintype "passive"))
    )
    (net (code "17") (name "/BF_DAT5") (class "Default")
      (node (ref "U18") (pin "23") (pinfunction "SDATA_23") (pintype "passive"))
      (node (ref "U21") (pin "34") (pinfunction "D_5_34") (pintype "passive"))
    )
    (net (code "18") (name "/BF_DAT6") (class "Default")
      (node (ref "U19") (pin "23") (pinfunction "SDATA_23") (pintype "passive"))
      (node (ref "U21") (pin "31") (pinfunction "D_6_31") (pintype "passive"))
    )
    (net (code "19") (name "/BF_DAT7") (class "Default")
      (node (ref "U20") (pin "23") (pinfunction "SDATA_23") (pintype "passive"))
      (node (ref "U21") (pin "28") (pinfunction "D_7_28") (pintype "passive"))
    )
    (net (code "20") (name "/BF_DAT8") (class "Default")
      (node (ref "U21") (pin "25") (pinfunction "D_8_25") (pintype "passive"))
      (node (ref "U22") (pin "23") (pinfunction "SDATA_23") (pintype "passive"))
    )
    (net (code "21") (name "/BF_DAT9") (class "Default")
      (node (ref "U21") (pin "22") (pinfunction "D_9_22") (pintype "passive"))
      (node (ref "U23") (pin "23") (pinfunction "SDATA_23") (pintype "passive"))
    )
    (net (code "22") (name "/BF_DAT10") (class "Default")
      (node (ref "U21") (pin "19") (pinfunction "D_10_19") (pintype "passive"))
      (node (ref "U24") (pin "23") (pinfunction "SDATA_23") (pintype "passive"))
    )
    (net (code "23") (name "/GND") (class "Default")
      (node (ref "C120") (pin "2") (pinfunction "2_2") (pintype "passive"))
      (node (ref "C72") (pin "2") (pinfunction "2_2") (pintype "passive"))
      (node (ref "C73") (pin "2") (pinfunction "2_2") (pintype "passive"))
      (node (ref "C74") (pin "2") (pinfunction "2_2") (pintype "passive"))
      (node (ref "C84") (pin "2") (pinfunction "2_2") (pintype "passive"))
      (node (ref "C85") (pin "2") (pinfunction "2_2") (pintype "passive"))
      (node (ref "C86") (pin "2") (pinfunction "2_2") (pintype "passive"))
      (node (ref "U13") (pin "36") (pinfunction "EP_36") (pintype "passive"))
      (node (ref "U21") (pin "41") (pinfunction "VSS_41") (pintype "passive"))
    )
    (net (code "24") (name "/PAR_1") (class "Default")
      (node (ref "U21") (pin "18") (pinfunction "PARITY_18") (pintype "passive"))
    )
    (net (code "25") (name "/PWR1") (class "Default")
      (node (ref "C72") (pin "1") (pinfunction "1_1") (pintype "passive"))
      (node (ref "C73") (pin "1") (pinfunction "1_1") (pintype "passive"))
      (node (ref "C74") (pin "1") (pinfunction "1_1") (pintype "passive"))
      (node (ref "C75") (pin "2") (pinfunction "2_2") (pintype "passive"))
      (node (ref "C76") (pin "2") (pinfunction "2_2") (pintype "passive"))
      (node (ref "C77") (pin "2") (pinfunction "2_2") (pintype "passive"))
      (node (ref "C84") (pin "1") (pinfunction "1_1") (pintype "passive"))
      (node (ref "C85") (pin "1") (pinfunction "1_1") (pintype "passive"))
      (node (ref "C86") (pin "1") (pinfunction "1_1") (pintype "passive"))
      (node (ref "C87") (pin "2") (pinfunction "2_2") (pintype "passive"))
      (node (ref "C88") (pin "2") (pinfunction "2_2") (pintype "passive"))
      (node (ref "C89") (pin "2") (pinfunction "2_2") (pintype "passive"))
      (node (ref "U13") (pin "1") (pinfunction "VDD_1") (pintype "passive"))
      (node (ref "U13") (pin "10") (pinfunction "VDD_10") (pintype "passive"))
      (node (ref "U13") (pin "11") (pinfunction "VDD_11") (pintype "passive"))
      (node (ref "U13") (pin "12") (pinfunction "VDD_12") (pintype "passive"))
      (node (ref "U13") (pin "13") (pinfunction "VDD_13") (pintype "passive"))
      (node (ref "U13") (pin "14") (pinfunction "VDD_14") (pintype "passive"))
      (node (ref "U13") (pin "15") (pinfunction "VDD_15") (pintype "passive"))
      (node (ref "U13") (pin "16") (pinfunction "VDD_16") (pintype "passive"))
      (node (ref "U13") (pin "17") (pinfunction "VDD_17") (pintype "passive"))
      (node (ref "U13") (pin "18") (pinfunction "VDD_18") (pintype "passive"))
      (node (ref "U13") (pin "19") (pinfunction "VDD_19") (pintype "passive"))
      (node (ref "U13") (pin "2") (pinfunction "VDD_2") (pintype "passive"))
      (node (ref "U13") (pin "20") (pinfunction "VDD_20") (pintype "passive"))
      (node (ref "U13") (pin "21") (pinfunction "VDD_21") (pintype "passive"))
      (node (ref "U13") (pin "24") (pinfunction "VDD_24") (pintype "passive"))
      (node (ref "U13") (pin "25") (pinfunction "VDD_25") (pintype "passive"))
      (node (ref "U13") (pin "26") (pinfunction "VDD_26") (pintype "passive"))
      (node (ref "U13") (pin "27") (pinfunction "VDD_27") (pintype "passive"))
      (node (ref "U13") (pin "28") (pinfunction "VDD_28") (pintype "passive"))
      (node (ref "U13") (pin "29") (pinfunction "VDD_29") (pintype "passive"))
      (node (ref "U13") (pin "3") (pinfunction "VDD_3") (pintype "passive"))
      (node (ref "U13") (pin "30") (pinfunction "VDD_30") (pintype "passive"))
      (node (ref "U13") (pin "31") (pinfunction "VDD_31") (pintype "passive"))
      (node (ref "U13") (pin "32") (pinfunction "VDD_32") (pintype "passive"))
      (node (ref "U13") (pin "33") (pinfunction "VDD_33") (pintype "passive"))
      (node (ref "U13") (pin "34") (pinfunction "VDD_34") (pintype "passive"))
      (node (ref "U13") (pin "35") (pinfunction "VDD_35") (pintype "passive"))
      (node (ref "U13") (pin "4") (pinfunction "VDD_4") (pintype "passive"))
      (node (ref "U13") (pin "5") (pinfunction "VDD_5") (pintype "passive"))
      (node (ref "U13") (pin "6") (pinfunction "VDD_6") (pintype "passive"))
      (node (ref "U13") (pin "7") (pinfunction "VDD_7") (pintype "passive"))
      (node (ref "U13") (pin "8") (pinfunction "VDD_8") (pintype "passive"))
      (node (ref "U13") (pin "9") (pinfunction "VDD_9") (pintype "passive"))
      (node (ref "U14") (pin "36") (pinfunction "EP_36") (pintype "passive"))
      (node (ref "U21") (pin "8") (pinfunction "V_0_8") (pintype "passive"))
    )
    (net (code "26") (name "/PWR2") (class "Default")
      (node (ref "C75") (pin "1") (pinfunction "1_1") (pintype "passive"))
      (node (ref "C76") (pin "1") (pinfunction "1_1") (pintype "passive"))
      (node (ref "C77") (pin "1") (pinfunction "1_1") (pintype "passive"))
      (node (ref "C78") (pin "2") (pinfunction "2_2") (pintype "passive"))
      (node (ref "C79") (pin "2") (pinfunction "2_2") (pintype "passive"))
      (node (ref "C80") (pin "2") (pinfunction "2_2") (pintype "passive"))
      (node (ref "C87") (pin "1") (pinfunction "1_1") (pintype "passive"))
      (node (ref "C88") (pin "1") (pinfunction "1_1") (pintype "passive"))
      (node (ref "C89") (pin "1") (pinfunction "1_1") (pintype "passive"))
      (node (ref "C90") (pin "2") (pinfunction "2_2") (pintype "passive"))
      (node (ref "C91") (pin "2") (pinfunction "2_2") (pintype "passive"))
      (node (ref "C92") (pin "2") (pinfunction "2_2") (pintype "passive"))
      (node (ref "U14") (pin "1") (pinfunction "VDD_1") (pintype "passive"))
      (node (ref "U14") (pin "10") (pinfunction "VDD_10") (pintype "passive"))
      (node (ref "U14") (pin "11") (pinfunction "VDD_11") (pintype "passive"))
      (node (ref "U14") (pin "12") (pinfunction "VDD_12") (pintype "passive"))
      (node (ref "U14") (pin "13") (pinfunction "VDD_13") (pintype "passive"))
      (node (ref "U14") (pin "14") (pinfunction "VDD_14") (pintype "passive"))
      (node (ref "U14") (pin "15") (pinfunction "VDD_15") (pintype "passive"))
      (node (ref "U14") (pin "16") (pinfunction "VDD_16") (pintype "passive"))
      (node (ref "U14") (pin "17") (pinfunction "VDD_17") (pintype "passive"))
      (node (ref "U14") (pin "18") (pinfunction "VDD_18") (pintype "passive"))
      (node (ref "U14") (pin "19") (pinfunction "VDD_19") (pintype "passive"))
      (node (ref "U14") (pin "2") (pinfunction "VDD_2") (pintype "passive"))
      (node (ref "U14") (pin "20") (pinfunction "VDD_20") (pintype "passive"))
      (node (ref "U14") (pin "21") (pinfunction "VDD_21") (pintype "passive"))
      (node (ref "U14") (pin "24") (pinfunction "VDD_24") (pintype "passive"))
      (node (ref "U14") (pin "25") (pinfunction "VDD_25") (pintype "passive"))
      (node (ref "U14") (pin "26") (pinfunction "VDD_26") (pintype "passive"))
      (node (ref "U14") (pin "27") (pinfunction "VDD_27") (pintype "passive"))
      (node (ref "U14") (pin "28") (pinfunction "VDD_28") (pintype "passive"))
      (node (ref "U14") (pin "29") (pinfunction "VDD_29") (pintype "passive"))
      (node (ref "U14") (pin "3") (pinfunction "VDD_3") (pintype "passive"))
      (node (ref "U14") (pin "30") (pinfunction "VDD_30") (pintype "passive"))
      (node (ref "U14") (pin "31") (pinfunction "VDD_31") (pintype "passive"))
      (node (ref "U14") (pin "32") (pinfunction "VDD_32") (pintype "passive"))
      (node (ref "U14") (pin "33") (pinfunction "VDD_33") (pintype "passive"))
      (node (ref "U14") (pin "34") (pinfunction "VDD_34") (pintype "passive"))
      (node (ref "U14") (pin "35") (pinfunction "VDD_35") (pintype "passive"))
      (node (ref "U14") (pin "4") (pinfunction "VDD_4") (pintype "passive"))
      (node (ref "U14") (pin "5") (pinfunction "VDD_5") (pintype "passive"))
      (node (ref "U14") (pin "6") (pinfunction "VDD_6") (pintype "passive"))
      (node (ref "U14") (pin "7") (pinfunction "VDD_7") (pintype "passive"))
      (node (ref "U14") (pin "8") (pinfunction "VDD_8") (pintype "passive"))
      (node (ref "U14") (pin "9") (pinfunction "VDD_9") (pintype "passive"))
      (node (ref "U15") (pin "36") (pinfunction "EP_36") (pintype "passive"))
      (node (ref "U21") (pin "5") (pinfunction "V_1_5") (pintype "passive"))
    )
    (net (code "27") (name "/PWR3") (class "Default")
      (node (ref "C78") (pin "1") (pinfunction "1_1") (pintype "passive"))
      (node (ref "C79") (pin "1") (pinfunction "1_1") (pintype "passive"))
      (node (ref "C80") (pin "1") (pinfunction "1_1") (pintype "passive"))
      (node (ref "C81") (pin "2") (pinfunction "2_2") (pintype "passive"))
      (node (ref "C82") (pin "2") (pinfunction "2_2") (pintype "passive"))
      (node (ref "C83") (pin "2") (pinfunction "2_2") (pintype "passive"))
      (node (ref "C90") (pin "1") (pinfunction "1_1") (pintype "passive"))
      (node (ref "C91") (pin "1") (pinfunction "1_1") (pintype "passive"))
      (node (ref "C92") (pin "1") (pinfunction "1_1") (pintype "passive"))
      (node (ref "C93") (pin "2") (pinfunction "2_2") (pintype "passive"))
      (node (ref "C94") (pin "2") (pinfunction "2_2") (pintype "passive"))
      (node (ref "C95") (pin "2") (pinfunction "2_2") (pintype "passive"))
      (node (ref "U15") (pin "1") (pinfunction "VDD_1") (pintype "passive"))
      (node (ref "U15") (pin "10") (pinfunction "VDD_10") (pintype "passive"))
      (node (ref "U15") (pin "11") (pinfunction "VDD_11") (pintype "passive"))
      (node (ref "U15") (pin "12") (pinfunction "VDD_12") (pintype "passive"))
      (node (ref "U15") (pin "13") (pinfunction "VDD_13") (pintype "passive"))
      (node (ref "U15") (pin "14") (pinfunction "VDD_14") (pintype "passive"))
      (node (ref "U15") (pin "15") (pinfunction "VDD_15") (pintype "passive"))
      (node (ref "U15") (pin "16") (pinfunction "VDD_16") (pintype "passive"))
      (node (ref "U15") (pin "17") (pinfunction "VDD_17") (pintype "passive"))
      (node (ref "U15") (pin "18") (pinfunction "VDD_18") (pintype "passive"))
      (node (ref "U15") (pin "19") (pinfunction "VDD_19") (pintype "passive"))
      (node (ref "U15") (pin "2") (pinfunction "VDD_2") (pintype "passive"))
      (node (ref "U15") (pin "20") (pinfunction "VDD_20") (pintype "passive"))
      (node (ref "U15") (pin "21") (pinfunction "VDD_21") (pintype "passive"))
      (node (ref "U15") (pin "24") (pinfunction "VDD_24") (pintype "passive"))
      (node (ref "U15") (pin "25") (pinfunction "VDD_25") (pintype "passive"))
      (node (ref "U15") (pin "26") (pinfunction "VDD_26") (pintype "passive"))
      (node (ref "U15") (pin "27") (pinfunction "VDD_27") (pintype "passive"))
      (node (ref "U15") (pin "28") (pinfunction "VDD_28") (pintype "passive"))
      (node (ref "U15") (pin "29") (pinfunction "VDD_29") (pintype "passive"))
      (node (ref "U15") (pin "3") (pinfunction "VDD_3") (pintype "passive"))
      (node (ref "U15") (pin "30") (pinfunction "VDD_30") (pintype "passive"))
      (node (ref "U15") (pin "31") (pinfunction "VDD_31") (pintype "passive"))
      (node (ref "U15") (pin "32") (pinfunction "VDD_32") (pintype "passive"))
      (node (ref "U15") (pin "33") (pinfunction "VDD_33") (pintype "passive"))
      (node (ref "U15") (pin "34") (pinfunction "VDD_34") (pintype "passive"))
      (node (ref "U15") (pin "35") (pinfunction "VDD_35") (pintype "passive"))
      (node (ref "U15") (pin "4") (pinfunction "VDD_4") (pintype "passive"))
      (node (ref "U15") (pin "5") (pinfunction "VDD_5") (pintype "passive"))
      (node (ref "U15") (pin "6") (pinfunction "VDD_6") (pintype "passive"))
      (node (ref "U15") (pin "7") (pinfunction "VDD_7") (pintype "passive"))
      (node (ref "U15") (pin "8") (pinfunction "VDD_8") (pintype "passive"))
      (node (ref "U15") (pin "9") (pinfunction "VDD_9") (pintype "passive"))
      (node (ref "U16") (pin "36") (pinfunction "EP_36") (pintype "passive"))
      (node (ref "U21") (pin "2") (pinfunction "V_2_2") (pintype "passive"))
    )
    (net (code "28") (name "/PWR4") (class "Default")
      (node (ref "C108") (pin "2") (pinfunction "2_2") (pintype "passive"))
      (node (ref "C109") (pin "2") (pinfunction "2_2") (pintype "passive"))
      (node (ref "C110") (pin "2") (pinfunction "2_2") (pintype "passive"))
      (node (ref "C81") (pin "1") (pinfunction "1_1") (pintype "passive"))
      (node (ref "C82") (pin "1") (pinfunction "1_1") (pintype "passive"))
      (node (ref "C83") (pin "1") (pinfunction "1_1") (pintype "passive"))
      (node (ref "C93") (pin "1") (pinfunction "1_1") (pintype "passive"))
      (node (ref "C94") (pin "1") (pinfunction "1_1") (pintype "passive"))
      (node (ref "C95") (pin "1") (pinfunction "1_1") (pintype "passive"))
      (node (ref "C96") (pin "2") (pinfunction "2_2") (pintype "passive"))
      (node (ref "C97") (pin "2") (pinfunction "2_2") (pintype "passive"))
      (node (ref "C98") (pin "2") (pinfunction "2_2") (pintype "passive"))
      (node (ref "U16") (pin "1") (pinfunction "VDD_1") (pintype "passive"))
      (node (ref "U16") (pin "10") (pinfunction "VDD_10") (pintype "passive"))
      (node (ref "U16") (pin "11") (pinfunction "VDD_11") (pintype "passive"))
      (node (ref "U16") (pin "12") (pinfunction "VDD_12") (pintype "passive"))
      (node (ref "U16") (pin "13") (pinfunction "VDD_13") (pintype "passive"))
      (node (ref "U16") (pin "14") (pinfunction "VDD_14") (pintype "passive"))
      (node (ref "U16") (pin "15") (pinfunction "VDD_15") (pintype "passive"))
      (node (ref "U16") (pin "16") (pinfunction "VDD_16") (pintype "passive"))
      (node (ref "U16") (pin "17") (pinfunction "VDD_17") (pintype "passive"))
      (node (ref "U16") (pin "18") (pinfunction "VDD_18") (pintype "passive"))
      (node (ref "U16") (pin "19") (pinfunction "VDD_19") (pintype "passive"))
      (node (ref "U16") (pin "2") (pinfunction "VDD_2") (pintype "passive"))
      (node (ref "U16") (pin "20") (pinfunction "VDD_20") (pintype "passive"))
      (node (ref "U16") (pin "21") (pinfunction "VDD_21") (pintype "passive"))
      (node (ref "U16") (pin "24") (pinfunction "VDD_24") (pintype "passive"))
      (node (ref "U16") (pin "25") (pinfunction "VDD_25") (pintype "passive"))
      (node (ref "U16") (pin "26") (pinfunction "VDD_26") (pintype "passive"))
      (node (ref "U16") (pin "27") (pinfunction "VDD_27") (pintype "passive"))
      (node (ref "U16") (pin "28") (pinfunction "VDD_28") (pintype "passive"))
      (node (ref "U16") (pin "29") (pinfunction "VDD_29") (pintype "passive"))
      (node (ref "U16") (pin "3") (pinfunction "VDD_3") (pintype "passive"))
      (node (ref "U16") (pin "30") (pinfunction "VDD_30") (pintype "passive"))
      (node (ref "U16") (pin "31") (pinfunction "VDD_31") (pintype "passive"))
      (node (ref "U16") (pin "32") (pinfunction "VDD_32") (pintype "passive"))
      (node (ref "U16") (pin "33") (pinfunction "VDD_33") (pintype "passive"))
      (node (ref "U16") (pin "34") (pinfunction "VDD_34") (pintype "passive"))
      (node (ref "U16") (pin "35") (pinfunction "VDD_35") (pintype "passive"))
      (node (ref "U16") (pin "4") (pinfunction "VDD_4") (pintype "passive"))
      (node (ref "U16") (pin "5") (pinfunction "VDD_5") (pintype "passive"))
      (node (ref "U16") (pin "6") (pinfunction "VDD_6") (pintype "passive"))
      (node (ref "U16") (pin "7") (pinfunction "VDD_7") (pintype "passive"))
      (node (ref "U16") (pin "8") (pinfunction "VDD_8") (pintype "passive"))
      (node (ref "U16") (pin "9") (pinfunction "VDD_9") (pintype "passive"))
      (node (ref "U17") (pin "36") (pinfunction "EP_36") (pintype "passive"))
      (node (ref "U21") (pin "39") (pinfunction "V_3_39") (pintype "passive"))
    )
    (net (code "29") (name "/PWR5") (class "Default")
      (node (ref "C100") (pin "2") (pinfunction "2_2") (pintype "passive"))
      (node (ref "C101") (pin "2") (pinfunction "2_2") (pintype "passive"))
      (node (ref "C108") (pin "1") (pinfunction "1_1") (pintype "passive"))
      (node (ref "C109") (pin "1") (pinfunction "1_1") (pintype "passive"))
      (node (ref "C110") (pin "1") (pinfunction "1_1") (pintype "passive"))
      (node (ref "C111") (pin "2") (pinfunction "2_2") (pintype "passive"))
      (node (ref "C112") (pin "2") (pinfunction "2_2") (pintype "passive"))
      (node (ref "C113") (pin "2") (pinfunction "2_2") (pintype "passive"))
      (node (ref "C96") (pin "1") (pinfunction "1_1") (pintype "passive"))
      (node (ref "C97") (pin "1") (pinfunction "1_1") (pintype "passive"))
      (node (ref "C98") (pin "1") (pinfunction "1_1") (pintype "passive"))
      (node (ref "C99") (pin "2") (pinfunction "2_2") (pintype "passive"))
      (node (ref "U17") (pin "1") (pinfunction "VDD_1") (pintype "passive"))
      (node (ref "U17") (pin "10") (pinfunction "VDD_10") (pintype "passive"))
      (node (ref "U17") (pin "11") (pinfunction "VDD_11") (pintype "passive"))
      (node (ref "U17") (pin "12") (pinfunction "VDD_12") (pintype "passive"))
      (node (ref "U17") (pin "13") (pinfunction "VDD_13") (pintype "passive"))
      (node (ref "U17") (pin "14") (pinfunction "VDD_14") (pintype "passive"))
      (node (ref "U17") (pin "15") (pinfunction "VDD_15") (pintype "passive"))
      (node (ref "U17") (pin "16") (pinfunction "VDD_16") (pintype "passive"))
      (node (ref "U17") (pin "17") (pinfunction "VDD_17") (pintype "passive"))
      (node (ref "U17") (pin "18") (pinfunction "VDD_18") (pintype "passive"))
      (node (ref "U17") (pin "19") (pinfunction "VDD_19") (pintype "passive"))
      (node (ref "U17") (pin "2") (pinfunction "VDD_2") (pintype "passive"))
      (node (ref "U17") (pin "20") (pinfunction "VDD_20") (pintype "passive"))
      (node (ref "U17") (pin "21") (pinfunction "VDD_21") (pintype "passive"))
      (node (ref "U17") (pin "24") (pinfunction "VDD_24") (pintype "passive"))
      (node (ref "U17") (pin "25") (pinfunction "VDD_25") (pintype "passive"))
      (node (ref "U17") (pin "26") (pinfunction "VDD_26") (pintype "passive"))
      (node (ref "U17") (pin "27") (pinfunction "VDD_27") (pintype "passive"))
      (node (ref "U17") (pin "28") (pinfunction "VDD_28") (pintype "passive"))
      (node (ref "U17") (pin "29") (pinfunction "VDD_29") (pintype "passive"))
      (node (ref "U17") (pin "3") (pinfunction "VDD_3") (pintype "passive"))
      (node (ref "U17") (pin "30") (pinfunction "VDD_30") (pintype "passive"))
      (node (ref "U17") (pin "31") (pinfunction "VDD_31") (pintype "passive"))
      (node (ref "U17") (pin "32") (pinfunction "VDD_32") (pintype "passive"))
      (node (ref "U17") (pin "33") (pinfunction "VDD_33") (pintype "passive"))
      (node (ref "U17") (pin "34") (pinfunction "VDD_34") (pintype "passive"))
      (node (ref "U17") (pin "35") (pinfunction "VDD_35") (pintype "passive"))
      (node (ref "U17") (pin "4") (pinfunction "VDD_4") (pintype "passive"))
      (node (ref "U17") (pin "5") (pinfunction "VDD_5") (pintype "passive"))
      (node (ref "U17") (pin "6") (pinfunction "VDD_6") (pintype "passive"))
      (node (ref "U17") (pin "7") (pinfunction "VDD_7") (pintype "passive"))
      (node (ref "U17") (pin "8") (pinfunction "VDD_8") (pintype "passive"))
      (node (ref "U17") (pin "9") (pinfunction "VDD_9") (pintype "passive"))
      (node (ref "U18") (pin "36") (pinfunction "EP_36") (pintype "passive"))
      (node (ref "U21") (pin "36") (pinfunction "V_4_36") (pintype "passive"))
    )
    (net (code "30") (name "/PWR6") (class "Default")
      (node (ref "C100") (pin "1") (pinfunction "1_1") (pintype "passive"))
      (node (ref "C101") (pin "1") (pinfunction "1_1") (pintype "passive"))
      (node (ref "C102") (pin "2") (pinfunction "2_2") (pintype "passive"))
      (node (ref "C103") (pin "2") (pinfunction "2_2") (pintype "passive"))
      (node (ref "C104") (pin "2") (pinfunction "2_2") (pintype "passive"))
      (node (ref "C111") (pin "1") (pinfunction "1_1") (pintype "passive"))
      (node (ref "C112") (pin "1") (pinfunction "1_1") (pintype "passive"))
      (node (ref "C113") (pin "1") (pinfunction "1_1") (pintype "passive"))
      (node (ref "C114") (pin "2") (pinfunction "2_2") (pintype "passive"))
      (node (ref "C115") (pin "2") (pinfunction "2_2") (pintype "passive"))
      (node (ref "C116") (pin "2") (pinfunction "2_2") (pintype "passive"))
      (node (ref "C99") (pin "1") (pinfunction "1_1") (pintype "passive"))
      (node (ref "U18") (pin "1") (pinfunction "VDD_1") (pintype "passive"))
      (node (ref "U18") (pin "10") (pinfunction "VDD_10") (pintype "passive"))
      (node (ref "U18") (pin "11") (pinfunction "VDD_11") (pintype "passive"))
      (node (ref "U18") (pin "12") (pinfunction "VDD_12") (pintype "passive"))
      (node (ref "U18") (pin "13") (pinfunction "VDD_13") (pintype "passive"))
      (node (ref "U18") (pin "14") (pinfunction "VDD_14") (pintype "passive"))
      (node (ref "U18") (pin "15") (pinfunction "VDD_15") (pintype "passive"))
      (node (ref "U18") (pin "16") (pinfunction "VDD_16") (pintype "passive"))
      (node (ref "U18") (pin "17") (pinfunction "VDD_17") (pintype "passive"))
      (node (ref "U18") (pin "18") (pinfunction "VDD_18") (pintype "passive"))
      (node (ref "U18") (pin "19") (pinfunction "VDD_19") (pintype "passive"))
      (node (ref "U18") (pin "2") (pinfunction "VDD_2") (pintype "passive"))
      (node (ref "U18") (pin "20") (pinfunction "VDD_20") (pintype "passive"))
      (node (ref "U18") (pin "21") (pinfunction "VDD_21") (pintype "passive"))
      (node (ref "U18") (pin "24") (pinfunction "VDD_24") (pintype "passive"))
      (node (ref "U18") (pin "25") (pinfunction "VDD_25") (pintype "passive"))
      (node (ref "U18") (pin "26") (pinfunction "VDD_26") (pintype "passive"))
      (node (ref "U18") (pin "27") (pinfunction "VDD_27") (pintype "passive"))
      (node (ref "U18") (pin "28") (pinfunction "VDD_28") (pintype "passive"))
      (node (ref "U18") (pin "29") (pinfunction "VDD_29") (pintype "passive"))
      (node (ref "U18") (pin "3") (pinfunction "VDD_3") (pintype "passive"))
      (node (ref "U18") (pin "30") (pinfunction "VDD_30") (pintype "passive"))
      (node (ref "U18") (pin "31") (pinfunction "VDD_31") (pintype "passive"))
      (node (ref "U18") (pin "32") (pinfunction "VDD_32") (pintype "passive"))
      (node (ref "U18") (pin "33") (pinfunction "VDD_33") (pintype "passive"))
      (node (ref "U18") (pin "34") (pinfunction "VDD_34") (pintype "passive"))
      (node (ref "U18") (pin "35") (pinfunction "VDD_35") (pintype "passive"))
      (node (ref "U18") (pin "4") (pinfunction "VDD_4") (pintype "passive"))
      (node (ref "U18") (pin "5") (pinfunction "VDD_5") (pintype "passive"))
      (node (ref "U18") (pin "6") (pinfunction "VDD_6") (pintype "passive"))
      (node (ref "U18") (pin "7") (pinfunction "VDD_7") (pintype "passive"))
      (node (ref "U18") (pin "8") (pinfunction "VDD_8") (pintype "passive"))
      (node (ref "U18") (pin "9") (pinfunction "VDD_9") (pintype "passive"))
      (node (ref "U19") (pin "36") (pinfunction "EP_36") (pintype "passive"))
      (node (ref "U21") (pin "33") (pinfunction "V_5_33") (pintype "passive"))
    )
    (net (code "31") (name "/PWR7") (class "Default")
      (node (ref "C102") (pin "1") (pinfunction "1_1") (pintype "passive"))
      (node (ref "C103") (pin "1") (pinfunction "1_1") (pintype "passive"))
      (node (ref "C104") (pin "1") (pinfunction "1_1") (pintype "passive"))
      (node (ref "C105") (pin "2") (pinfunction "2_2") (pintype "passive"))
      (node (ref "C106") (pin "2") (pinfunction "2_2") (pintype "passive"))
      (node (ref "C107") (pin "2") (pinfunction "2_2") (pintype "passive"))
      (node (ref "C114") (pin "1") (pinfunction "1_1") (pintype "passive"))
      (node (ref "C115") (pin "1") (pinfunction "1_1") (pintype "passive"))
      (node (ref "C116") (pin "1") (pinfunction "1_1") (pintype "passive"))
      (node (ref "C117") (pin "2") (pinfunction "2_2") (pintype "passive"))
      (node (ref "C118") (pin "2") (pinfunction "2_2") (pintype "passive"))
      (node (ref "C119") (pin "2") (pinfunction "2_2") (pintype "passive"))
      (node (ref "U19") (pin "1") (pinfunction "VDD_1") (pintype "passive"))
      (node (ref "U19") (pin "10") (pinfunction "VDD_10") (pintype "passive"))
      (node (ref "U19") (pin "11") (pinfunction "VDD_11") (pintype "passive"))
      (node (ref "U19") (pin "12") (pinfunction "VDD_12") (pintype "passive"))
      (node (ref "U19") (pin "13") (pinfunction "VDD_13") (pintype "passive"))
      (node (ref "U19") (pin "14") (pinfunction "VDD_14") (pintype "passive"))
      (node (ref "U19") (pin "15") (pinfunction "VDD_15") (pintype "passive"))
      (node (ref "U19") (pin "16") (pinfunction "VDD_16") (pintype "passive"))
      (node (ref "U19") (pin "17") (pinfunction "VDD_17") (pintype "passive"))
      (node (ref "U19") (pin "18") (pinfunction "VDD_18") (pintype "passive"))
      (node (ref "U19") (pin "19") (pinfunction "VDD_19") (pintype "passive"))
      (node (ref "U19") (pin "2") (pinfunction "VDD_2") (pintype "passive"))
      (node (ref "U19") (pin "20") (pinfunction "VDD_20") (pintype "passive"))
      (node (ref "U19") (pin "21") (pinfunction "VDD_21") (pintype "passive"))
      (node (ref "U19") (pin "24") (pinfunction "VDD_24") (pintype "passive"))
      (node (ref "U19") (pin "25") (pinfunction "VDD_25") (pintype "passive"))
      (node (ref "U19") (pin "26") (pinfunction "VDD_26") (pintype "passive"))
      (node (ref "U19") (pin "27") (pinfunction "VDD_27") (pintype "passive"))
      (node (ref "U19") (pin "28") (pinfunction "VDD_28") (pintype "passive"))
      (node (ref "U19") (pin "29") (pinfunction "VDD_29") (pintype "passive"))
      (node (ref "U19") (pin "3") (pinfunction "VDD_3") (pintype "passive"))
      (node (ref "U19") (pin "30") (pinfunction "VDD_30") (pintype "passive"))
      (node (ref "U19") (pin "31") (pinfunction "VDD_31") (pintype "passive"))
      (node (ref "U19") (pin "32") (pinfunction "VDD_32") (pintype "passive"))
      (node (ref "U19") (pin "33") (pinfunction "VDD_33") (pintype "passive"))
      (node (ref "U19") (pin "34") (pinfunction "VDD_34") (pintype "passive"))
      (node (ref "U19") (pin "35") (pinfunction "VDD_35") (pintype "passive"))
      (node (ref "U19") (pin "4") (pinfunction "VDD_4") (pintype "passive"))
      (node (ref "U19") (pin "5") (pinfunction "VDD_5") (pintype "passive"))
      (node (ref "U19") (pin "6") (pinfunction "VDD_6") (pintype "passive"))
      (node (ref "U19") (pin "7") (pinfunction "VDD_7") (pintype "passive"))
      (node (ref "U19") (pin "8") (pinfunction "VDD_8") (pintype "passive"))
      (node (ref "U19") (pin "9") (pinfunction "VDD_9") (pintype "passive"))
      (node (ref "U20") (pin "36") (pinfunction "EP_36") (pintype "passive"))
      (node (ref "U21") (pin "30") (pinfunction "V_6_30") (pintype "passive"))
    )
    (net (code "32") (name "/PWR8") (class "Default")
      (node (ref "C105") (pin "1") (pinfunction "1_1") (pintype "passive"))
      (node (ref "C106") (pin "1") (pinfunction "1_1") (pintype "passive"))
      (node (ref "C107") (pin "1") (pinfunction "1_1") (pintype "passive"))
      (node (ref "C117") (pin "1") (pinfunction "1_1") (pintype "passive"))
      (node (ref "C118") (pin "1") (pinfunction "1_1") (pintype "passive"))
      (node (ref "C119") (pin "1") (pinfunction "1_1") (pintype "passive"))
      (node (ref "C121") (pin "2") (pinfunction "2_2") (pintype "passive"))
      (node (ref "C122") (pin "2") (pinfunction "2_2") (pintype "passive"))
      (node (ref "C123") (pin "2") (pinfunction "2_2") (pintype "passive"))
      (node (ref "C130") (pin "2") (pinfunction "2_2") (pintype "passive"))
      (node (ref "C131") (pin "2") (pinfunction "2_2") (pintype "passive"))
      (node (ref "C132") (pin "2") (pinfunction "2_2") (pintype "passive"))
      (node (ref "U20") (pin "1") (pinfunction "VDD_1") (pintype "passive"))
      (node (ref "U20") (pin "10") (pinfunction "VDD_10") (pintype "passive"))
      (node (ref "U20") (pin "11") (pinfunction "VDD_11") (pintype "passive"))
      (node (ref "U20") (pin "12") (pinfunction "VDD_12") (pintype "passive"))
      (node (ref "U20") (pin "13") (pinfunction "VDD_13") (pintype "passive"))
      (node (ref "U20") (pin "14") (pinfunction "VDD_14") (pintype "passive"))
      (node (ref "U20") (pin "15") (pinfunction "VDD_15") (pintype "passive"))
      (node (ref "U20") (pin "16") (pinfunction "VDD_16") (pintype "passive"))
      (node (ref "U20") (pin "17") (pinfunction "VDD_17") (pintype "passive"))
      (node (ref "U20") (pin "18") (pinfunction "VDD_18") (pintype "passive"))
      (node (ref "U20") (pin "19") (pinfunction "VDD_19") (pintype "passive"))
      (node (ref "U20") (pin "2") (pinfunction "VDD_2") (pintype "passive"))
      (node (ref "U20") (pin "20") (pinfunction "VDD_20") (pintype "passive"))
      (node (ref "U20") (pin "21") (pinfunction "VDD_21") (pintype "passive"))
      (node (ref "U20") (pin "24") (pinfunction "VDD_24") (pintype "passive"))
      (node (ref "U20") (pin "25") (pinfunction "VDD_25") (pintype "passive"))
      (node (ref "U20") (pin "26") (pinfunction "VDD_26") (pintype "passive"))
      (node (ref "U20") (pin "27") (pinfunction "VDD_27") (pintype "passive"))
      (node (ref "U20") (pin "28") (pinfunction "VDD_28") (pintype "passive"))
      (node (ref "U20") (pin "29") (pinfunction "VDD_29") (pintype "passive"))
      (node (ref "U20") (pin "3") (pinfunction "VDD_3") (pintype "passive"))
      (node (ref "U20") (pin "30") (pinfunction "VDD_30") (pintype "passive"))
      (node (ref "U20") (pin "31") (pinfunction "VDD_31") (pintype "passive"))
      (node (ref "U20") (pin "32") (pinfunction "VDD_32") (pintype "passive"))
      (node (ref "U20") (pin "33") (pinfunction "VDD_33") (pintype "passive"))
      (node (ref "U20") (pin "34") (pinfunction "VDD_34") (pintype "passive"))
      (node (ref "U20") (pin "35") (pinfunction "VDD_35") (pintype "passive"))
      (node (ref "U20") (pin "4") (pinfunction "VDD_4") (pintype "passive"))
      (node (ref "U20") (pin "5") (pinfunction "VDD_5") (pintype "passive"))
      (node (ref "U20") (pin "6") (pinfunction "VDD_6") (pintype "passive"))
      (node (ref "U20") (pin "7") (pinfunction "VDD_7") (pintype "passive"))
      (node (ref "U20") (pin "8") (pinfunction "VDD_8") (pintype "passive"))
      (node (ref "U20") (pin "9") (pinfunction "VDD_9") (pintype "passive"))
      (node (ref "U21") (pin "27") (pinfunction "V_7_27") (pintype "passive"))
      (node (ref "U22") (pin "36") (pinfunction "EP_36") (pintype "passive"))
    )
    (net (code "33") (name "/PWR9") (class "Default")
      (node (ref "C121") (pin "1") (pinfunction "1_1") (pintype "passive"))
      (node (ref "C122") (pin "1") (pinfunction "1_1") (pintype "passive"))
      (node (ref "C123") (pin "1") (pinfunction "1_1") (pintype "passive"))
      (node (ref "C124") (pin "2") (pinfunction "2_2") (pintype "passive"))
      (node (ref "C125") (pin "2") (pinfunction "2_2") (pintype "passive"))
      (node (ref "C126") (pin "2") (pinfunction "2_2") (pintype "passive"))
      (node (ref "C130") (pin "1") (pinfunction "1_1") (pintype "passive"))
      (node (ref "C131") (pin "1") (pinfunction "1_1") (pintype "passive"))
      (node (ref "C132") (pin "1") (pinfunction "1_1") (pintype "passive"))
      (node (ref "C133") (pin "2") (pinfunction "2_2") (pintype "passive"))
      (node (ref "C134") (pin "2") (pinfunction "2_2") (pintype "passive"))
      (node (ref "C135") (pin "2") (pinfunction "2_2") (pintype "passive"))
      (node (ref "U21") (pin "24") (pinfunction "V_8_24") (pintype "passive"))
      (node (ref "U22") (pin "1") (pinfunction "VDD_1") (pintype "passive"))
      (node (ref "U22") (pin "10") (pinfunction "VDD_10") (pintype "passive"))
      (node (ref "U22") (pin "11") (pinfunction "VDD_11") (pintype "passive"))
      (node (ref "U22") (pin "12") (pinfunction "VDD_12") (pintype "passive"))
      (node (ref "U22") (pin "13") (pinfunction "VDD_13") (pintype "passive"))
      (node (ref "U22") (pin "14") (pinfunction "VDD_14") (pintype "passive"))
      (node (ref "U22") (pin "15") (pinfunction "VDD_15") (pintype "passive"))
      (node (ref "U22") (pin "16") (pinfunction "VDD_16") (pintype "passive"))
      (node (ref "U22") (pin "17") (pinfunction "VDD_17") (pintype "passive"))
      (node (ref "U22") (pin "18") (pinfunction "VDD_18") (pintype "passive"))
      (node (ref "U22") (pin "19") (pinfunction "VDD_19") (pintype "passive"))
      (node (ref "U22") (pin "2") (pinfunction "VDD_2") (pintype "passive"))
      (node (ref "U22") (pin "20") (pinfunction "VDD_20") (pintype "passive"))
      (node (ref "U22") (pin "21") (pinfunction "VDD_21") (pintype "passive"))
      (node (ref "U22") (pin "24") (pinfunction "VDD_24") (pintype "passive"))
      (node (ref "U22") (pin "25") (pinfunction "VDD_25") (pintype "passive"))
      (node (ref "U22") (pin "26") (pinfunction "VDD_26") (pintype "passive"))
      (node (ref "U22") (pin "27") (pinfunction "VDD_27") (pintype "passive"))
      (node (ref "U22") (pin "28") (pinfunction "VDD_28") (pintype "passive"))
      (node (ref "U22") (pin "29") (pinfunction "VDD_29") (pintype "passive"))
      (node (ref "U22") (pin "3") (pinfunction "VDD_3") (pintype "passive"))
      (node (ref "U22") (pin "30") (pinfunction "VDD_30") (pintype "passive"))
      (node (ref "U22") (pin "31") (pinfunction "VDD_31") (pintype "passive"))
      (node (ref "U22") (pin "32") (pinfunction "VDD_32") (pintype "passive"))
      (node (ref "U22") (pin "33") (pinfunction "VDD_33") (pintype "passive"))
      (node (ref "U22") (pin "34") (pinfunction "VDD_34") (pintype "passive"))
      (node (ref "U22") (pin "35") (pinfunction "VDD_35") (pintype "passive"))
      (node (ref "U22") (pin "4") (pinfunction "VDD_4") (pintype "passive"))
      (node (ref "U22") (pin "5") (pinfunction "VDD_5") (pintype "passive"))
      (node (ref "U22") (pin "6") (pinfunction "VDD_6") (pintype "passive"))
      (node (ref "U22") (pin "7") (pinfunction "VDD_7") (pintype "passive"))
      (node (ref "U22") (pin "8") (pinfunction "VDD_8") (pintype "passive"))
      (node (ref "U22") (pin "9") (pinfunction "VDD_9") (pintype "passive"))
      (node (ref "U23") (pin "36") (pinfunction "EP_36") (pintype "passive"))
    )
    (net (code "34") (name "/PWR10") (class "Default")
      (node (ref "C124") (pin "1") (pinfunction "1_1") (pintype "passive"))
      (node (ref "C125") (pin "1") (pinfunction "1_1") (pintype "passive"))
      (node (ref "C126") (pin "1") (pinfunction "1_1") (pintype "passive"))
      (node (ref "C127") (pin "2") (pinfunction "2_2") (pintype "passive"))
      (node (ref "C128") (pin "2") (pinfunction "2_2") (pintype "passive"))
      (node (ref "C129") (pin "2") (pinfunction "2_2") (pintype "passive"))
      (node (ref "C133") (pin "1") (pinfunction "1_1") (pintype "passive"))
      (node (ref "C134") (pin "1") (pinfunction "1_1") (pintype "passive"))
      (node (ref "C135") (pin "1") (pinfunction "1_1") (pintype "passive"))
      (node (ref "C136") (pin "2") (pinfunction "2_2") (pintype "passive"))
      (node (ref "C137") (pin "2") (pinfunction "2_2") (pintype "passive"))
      (node (ref "C138") (pin "2") (pinfunction "2_2") (pintype "passive"))
      (node (ref "U21") (pin "21") (pinfunction "V_9_21") (pintype "passive"))
      (node (ref "U23") (pin "1") (pinfunction "VDD_1") (pintype "passive"))
      (node (ref "U23") (pin "10") (pinfunction "VDD_10") (pintype "passive"))
      (node (ref "U23") (pin "11") (pinfunction "VDD_11") (pintype "passive"))
      (node (ref "U23") (pin "12") (pinfunction "VDD_12") (pintype "passive"))
      (node (ref "U23") (pin "13") (pinfunction "VDD_13") (pintype "passive"))
      (node (ref "U23") (pin "14") (pinfunction "VDD_14") (pintype "passive"))
      (node (ref "U23") (pin "15") (pinfunction "VDD_15") (pintype "passive"))
      (node (ref "U23") (pin "16") (pinfunction "VDD_16") (pintype "passive"))
      (node (ref "U23") (pin "17") (pinfunction "VDD_17") (pintype "passive"))
      (node (ref "U23") (pin "18") (pinfunction "VDD_18") (pintype "passive"))
      (node (ref "U23") (pin "19") (pinfunction "VDD_19") (pintype "passive"))
      (node (ref "U23") (pin "2") (pinfunction "VDD_2") (pintype "passive"))
      (node (ref "U23") (pin "20") (pinfunction "VDD_20") (pintype "passive"))
      (node (ref "U23") (pin "21") (pinfunction "VDD_21") (pintype "passive"))
      (node (ref "U23") (pin "24") (pinfunction "VDD_24") (pintype "passive"))
      (node (ref "U23") (pin "25") (pinfunction "VDD_25") (pintype "passive"))
      (node (ref "U23") (pin "26") (pinfunction "VDD_26") (pintype "passive"))
      (node (ref "U23") (pin "27") (pinfunction "VDD_27") (pintype "passive"))
      (node (ref "U23") (pin "28") (pinfunction "VDD_28") (pintype "passive"))
      (node (ref "U23") (pin "29") (pinfunction "VDD_29") (pintype "passive"))
      (node (ref "U23") (pin "3") (pinfunction "VDD_3") (pintype "passive"))
      (node (ref "U23") (pin "30") (pinfunction "VDD_30") (pintype "passive"))
      (node (ref "U23") (pin "31") (pinfunction "VDD_31") (pintype "passive"))
      (node (ref "U23") (pin "32") (pinfunction "VDD_32") (pintype "passive"))
      (node (ref "U23") (pin "33") (pinfunction "VDD_33") (pintype "passive"))
      (node (ref "U23") (pin "34") (pinfunction "VDD_34") (pintype "passive"))
      (node (ref "U23") (pin "35") (pinfunction "VDD_35") (pintype "passive"))
      (node (ref "U23") (pin "4") (pinfunction "VDD_4") (pintype "passive"))
      (node (ref "U23") (pin "5") (pinfunction "VDD_5") (pintype "passive"))
      (node (ref "U23") (pin "6") (pinfunction "VDD_6") (pintype "passive"))
      (node (ref "U23") (pin "7") (pinfunction "VDD_7") (pintype "passive"))
      (node (ref "U23") (pin "8") (pinfunction "VDD_8") (pintype "passive"))
      (node (ref "U23") (pin "9") (pinfunction "VDD_9") (pintype "passive"))
      (node (ref "U24") (pin "36") (pinfunction "EP_36") (pintype "passive"))
    )
    (net (code "35") (name "/PWR11") (class "Default")
      (node (ref "C120") (pin "1") (pinfunction "1_1") (pintype "passive"))
      (node (ref "C127") (pin "1") (pinfunction "1_1") (pintype "passive"))
      (node (ref "C128") (pin "1") (pinfunction "1_1") (pintype "passive"))
      (node (ref "C129") (pin "1") (pinfunction "1_1") (pintype "passive"))
      (node (ref "C136") (pin "1") (pinfunction "1_1") (pintype "passive"))
      (node (ref "C137") (pin "1") (pinfunction "1_1") (pintype "passive"))
      (node (ref "C138") (pin "1") (pinfunction "1_1") (pintype "passive"))
      (node (ref "U21") (pin "17") (pinfunction "VDD_17") (pintype "passive"))
      (node (ref "U24") (pin "1") (pinfunction "VDD_1") (pintype "passive"))
      (node (ref "U24") (pin "10") (pinfunction "VDD_10") (pintype "passive"))
      (node (ref "U24") (pin "11") (pinfunction "VDD_11") (pintype "passive"))
      (node (ref "U24") (pin "12") (pinfunction "VDD_12") (pintype "passive"))
      (node (ref "U24") (pin "13") (pinfunction "VDD_13") (pintype "passive"))
      (node (ref "U24") (pin "14") (pinfunction "VDD_14") (pintype "passive"))
      (node (ref "U24") (pin "15") (pinfunction "VDD_15") (pintype "passive"))
      (node (ref "U24") (pin "16") (pinfunction "VDD_16") (pintype "passive"))
      (node (ref "U24") (pin "17") (pinfunction "VDD_17") (pintype "passive"))
      (node (ref "U24") (pin "18") (pinfunction "VDD_18") (pintype "passive"))
      (node (ref "U24") (pin "19") (pinfunction "VDD_19") (pintype "passive"))
      (node (ref "U24") (pin "2") (pinfunction "VDD_2") (pintype "passive"))
      (node (ref "U24") (pin "20") (pinfunction "VDD_20") (pintype "passive"))
      (node (ref "U24") (pin "21") (pinfunction "VDD_21") (pintype "passive"))
      (node (ref "U24") (pin "24") (pinfunction "VDD_24") (pintype "passive"))
      (node (ref "U24") (pin "25") (pinfunction "VDD_25") (pintype "passive"))
      (node (ref "U24") (pin "26") (pinfunction "VDD_26") (pintype "passive"))
      (node (ref "U24") (pin "27") (pinfunction "VDD_27") (pintype "passive"))
      (node (ref "U24") (pin "28") (pinfunction "VDD_28") (pintype "passive"))
      (node (ref "U24") (pin "29") (pinfunction "VDD_29") (pintype "passive"))
      (node (ref "U24") (pin "3") (pinfunction "VDD_3") (pintype "passive"))
      (node (ref "U24") (pin "30") (pinfunction "VDD_30") (pintype "passive"))
      (node (ref "U24") (pin "31") (pinfunction "VDD_31") (pintype "passive"))
      (node (ref "U24") (pin "32") (pinfunction "VDD_32") (pintype "passive"))
      (node (ref "U24") (pin "33") (pinfunction "VDD_33") (pintype "passive"))
      (node (ref "U24") (pin "34") (pinfunction "VDD_34") (pintype "passive"))
      (node (ref "U24") (pin "35") (pinfunction "VDD_35") (pintype "passive"))
      (node (ref "U24") (pin "4") (pinfunction "VDD_4") (pintype "passive"))
      (node (ref "U24") (pin "5") (pinfunction "VDD_5") (pintype "passive"))
      (node (ref "U24") (pin "6") (pinfunction "VDD_6") (pintype "passive"))
      (node (ref "U24") (pin "7") (pinfunction "VDD_7") (pintype "passive"))
      (node (ref "U24") (pin "8") (pinfunction "VDD_8") (pintype "passive"))
      (node (ref "U24") (pin "9") (pinfunction "VDD_9") (pintype "passive"))
    )
    (net (code "36") (name "/RX0_1") (class "Default")
      (node (ref "U21") (pin "12") (pinfunction "RX_0_12") (pintype "passive"))
    )
    (net (code "37") (name "/RX1_1") (class "Default")
      (node (ref "U21") (pin "14") (pinfunction "RX_1_14") (pintype "passive"))
    )
    (net (code "38") (name "/RX2_1") (class "Default")
      (node (ref "U21") (pin "16") (pinfunction "RX_2_16") (pintype "passive"))
    )
    (net (code "39") (name "/TX0_1") (class "Default")
      (node (ref "U21") (pin "11") (pinfunction "TX_0_11") (pintype "passive"))
    )
    (net (code "40") (name "/TX1_1") (class "Default")
      (node (ref "U21") (pin "13") (pinfunction "TX_1_13") (pintype "passive"))
    )
    (net (code "41") (name "/TX2_1") (class "Default")
      (node (ref "U21") (pin "15") (pinfunction "TX_2_15") (pintype "passive"))
    )
  )
)
